# 1_P1_schdoc.net
KiCad netlist of a schematic drawn in Altium Designer
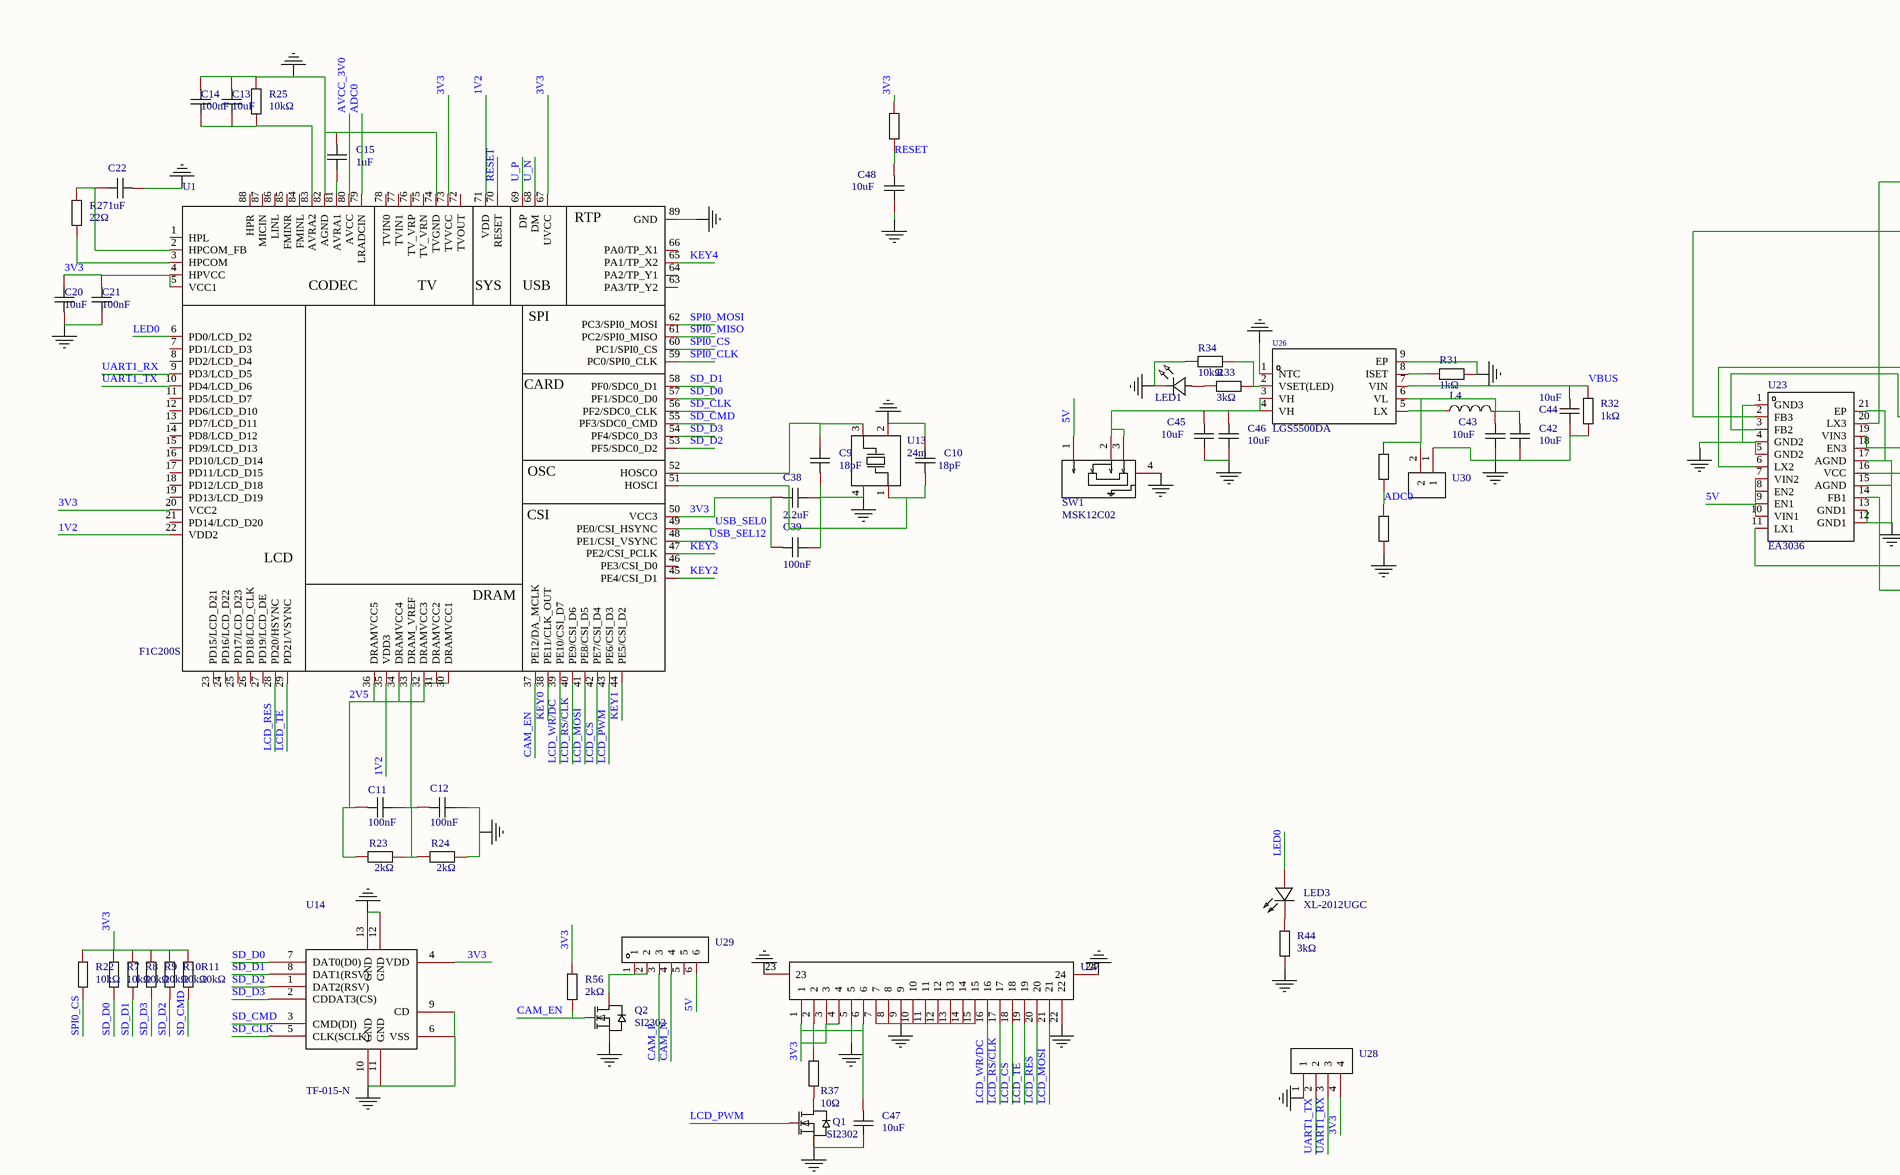
[diagram p0: 1_P1.schdoc.schdoc, top left]
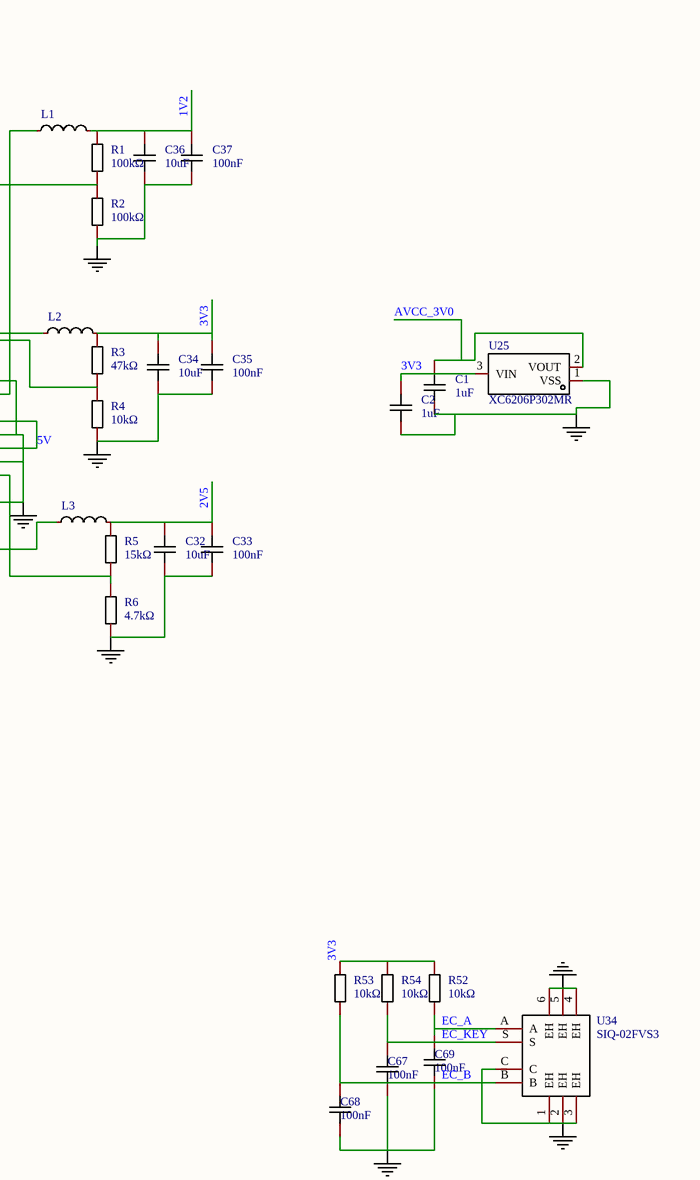
[diagram p1: 1_P1.schdoc.schdoc, top right]
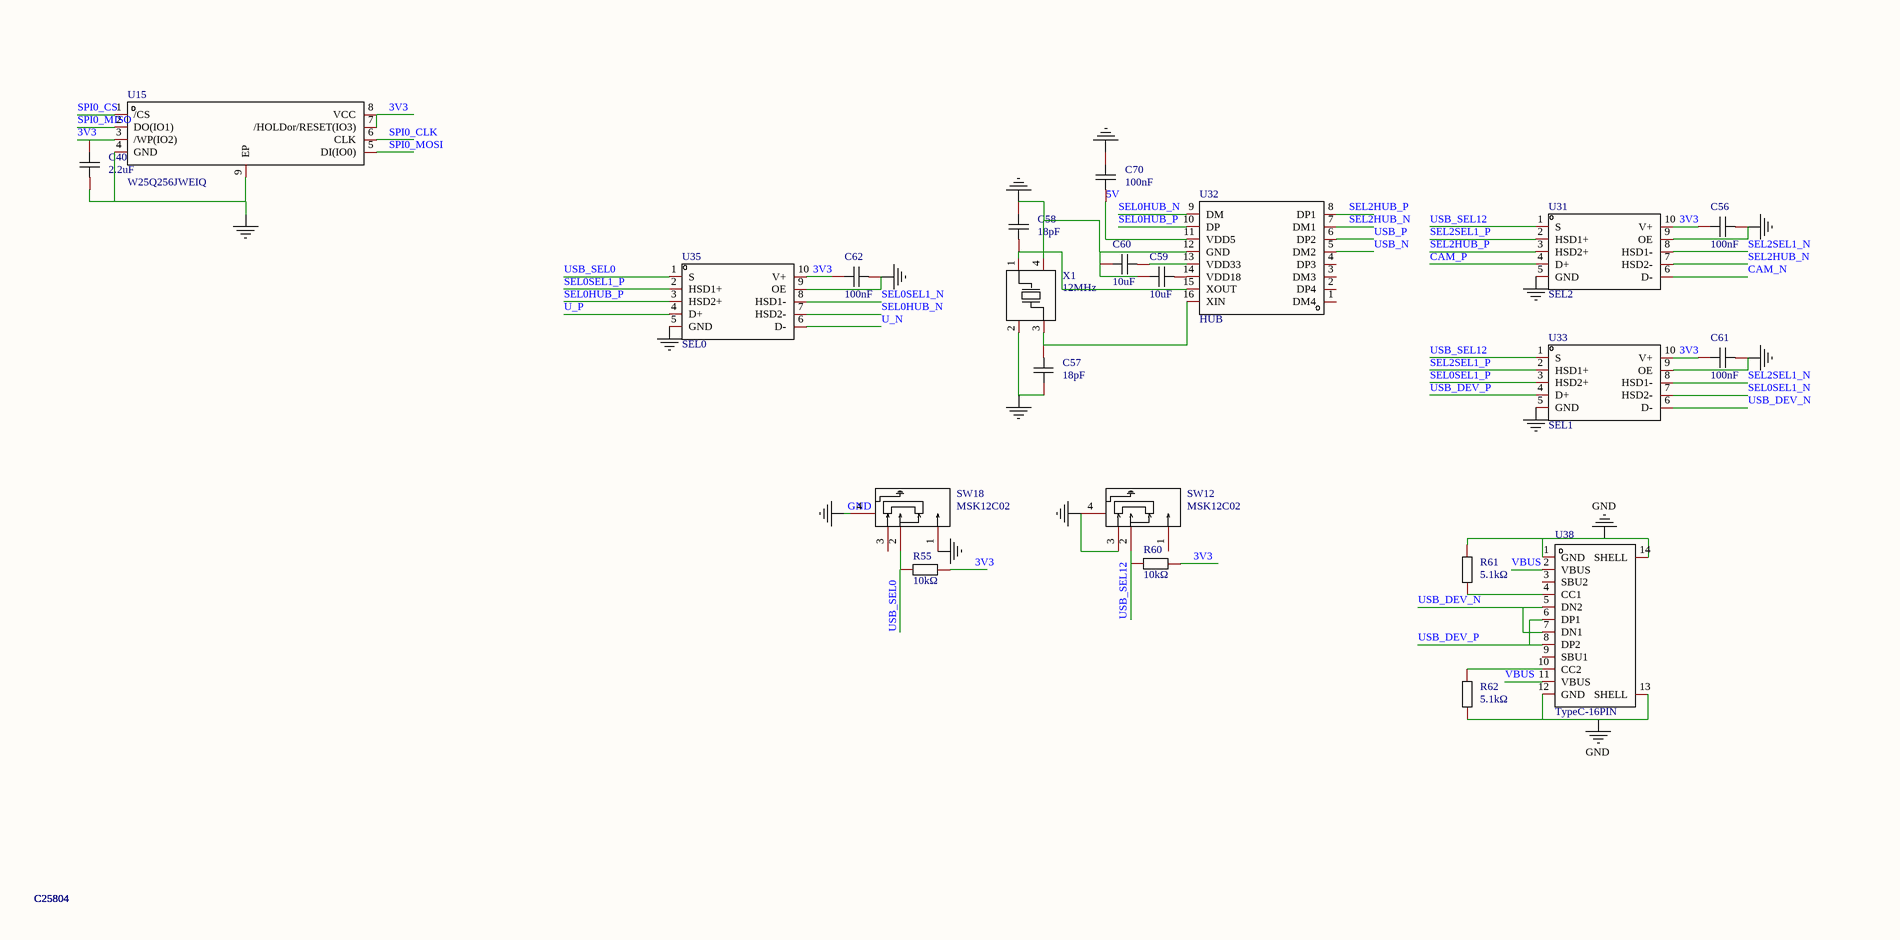
[diagram p2: 1_P1.schdoc.schdoc, bottom left]
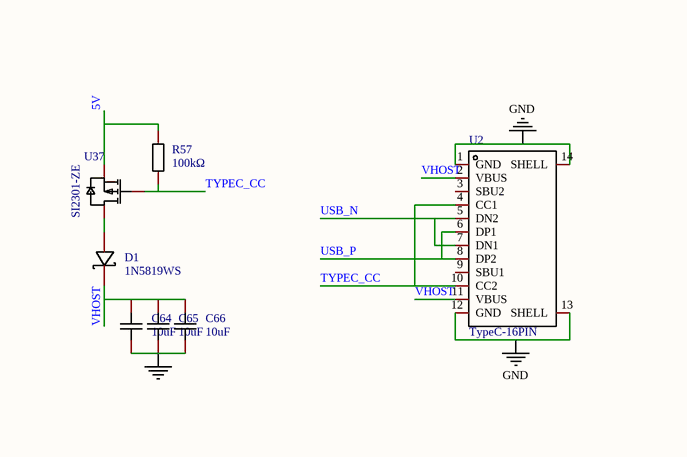
[diagram p3: 1_P1.schdoc.schdoc, bottom right]

(export (version "E")
  (design (tool "Eeschema 10.0.6"))
  (components
    (comp (ref "C1")
      (value "1uF")
      (fields
        (field (name "NAME") "1uF")
        (field (name "MANUFACTURER") "SAMSUNG(三星)")
        (field (name "MANUFACTURER PART") "CL10A105KB8NNNC")
        (field (name "TOLERANCE") "±10%")
      )
      (libsource (lib "altium-import") (part "root_1_CL10A105KB8NNNC_"))
    )
    (comp (ref "C2")
      (value "1uF")
      (fields
        (field (name "NAME") "1uF")
        (field (name "MANUFACTURER") "SAMSUNG(三星)")
        (field (name "MANUFACTURER PART") "CL10A105KB8NNNC")
        (field (name "TOLERANCE") "±10%")
      )
      (libsource (lib "altium-import") (part "root_1_CL10A105KB8NNNC_"))
    )
    (comp (ref "C9")
      (value "18pF")
      (fields
        (field (name "NAME") "18pF")
        (field (name "MANUFACTURER") "FH(风华)")
        (field (name "MANUFACTURER PART") "0402CG180J500NT")
        (field (name "TOLERANCE") "±5%")
      )
      (libsource (lib "altium-import") (part "root_3_0402CG180J500NT_"))
    )
    (comp (ref "C10")
      (value "18pF")
      (fields
        (field (name "NAME") "18pF")
        (field (name "MANUFACTURER") "FH(风华)")
        (field (name "MANUFACTURER PART") "0402CG180J500NT")
        (field (name "TOLERANCE") "±5%")
      )
      (libsource (lib "altium-import") (part "root_3_0402CG180J500NT_"))
    )
    (comp (ref "C11")
      (value "100nF")
      (fields
        (field (name "NAME") "100nF")
        (field (name "MANUFACTURER") "FH(风华)")
        (field (name "MANUFACTURER PART") "0603B104K500NT")
        (field (name "TOLERANCE") "±10%")
      )
      (libsource (lib "altium-import") (part "root_2_0603B104K500NT_"))
    )
    (comp (ref "C12")
      (value "100nF")
      (fields
        (field (name "NAME") "100nF")
        (field (name "MANUFACTURER") "FH(风华)")
        (field (name "MANUFACTURER PART") "0603B104K500NT")
        (field (name "TOLERANCE") "±10%")
      )
      (libsource (lib "altium-import") (part "root_2_0603B104K500NT_"))
    )
    (comp (ref "C13")
      (value "10uF")
      (fields
        (field (name "NAME") "10uF")
        (field (name "MANUFACTURER") "SAMSUNG(三星)")
        (field (name "MANUFACTURER PART") "CL10A106MA8NRNC")
        (field (name "TOLERANCE") "±20%")
      )
      (libsource (lib "altium-import") (part "root_1_CL10A106MA8NRNC_"))
    )
    (comp (ref "C14")
      (value "100nF")
      (fields
        (field (name "NAME") "100nF")
        (field (name "MANUFACTURER") "FH(风华)")
        (field (name "MANUFACTURER PART") "0603B104K500NT")
        (field (name "TOLERANCE") "±10%")
      )
      (libsource (lib "altium-import") (part "root_1_0603B104K500NT_"))
    )
    (comp (ref "C15")
      (value "1uF")
      (fields
        (field (name "NAME") "1uF")
        (field (name "MANUFACTURER") "SAMSUNG(三星)")
        (field (name "MANUFACTURER PART") "CL10A105KB8NNNC")
        (field (name "TOLERANCE") "±10%")
      )
      (libsource (lib "altium-import") (part "root_1_CL10A105KB8NNNC_"))
    )
    (comp (ref "C20")
      (value "10uF")
      (fields
        (field (name "NAME") "10uF")
        (field (name "MANUFACTURER") "SAMSUNG(三星)")
        (field (name "MANUFACTURER PART") "CL10A106MA8NRNC")
        (field (name "TOLERANCE") "±20%")
      )
      (libsource (lib "altium-import") (part "root_3_CL10A106MA8NRNC_"))
    )
    (comp (ref "C21")
      (value "100nF")
      (fields
        (field (name "NAME") "100nF")
        (field (name "MANUFACTURER") "FH(风华)")
        (field (name "MANUFACTURER PART") "0603B104K500NT")
        (field (name "TOLERANCE") "±10%")
      )
      (libsource (lib "altium-import") (part "root_1_0603B104K500NT_"))
    )
    (comp (ref "C22")
      (value "1uF")
      (fields
        (field (name "NAME") "1uF")
        (field (name "MANUFACTURER") "SAMSUNG(三星)")
        (field (name "MANUFACTURER PART") "CL10A105KB8NNNC")
        (field (name "TOLERANCE") "±10%")
      )
      (libsource (lib "altium-import") (part "root_0_CL10A105KB8NNNC_"))
    )
    (comp (ref "C32")
      (value "10uF")
      (fields
        (field (name "NAME") "10uF")
        (field (name "MANUFACTURER") "SAMSUNG(三星)")
        (field (name "MANUFACTURER PART") "CL10A106MA8NRNC")
        (field (name "TOLERANCE") "±20%")
      )
      (libsource (lib "altium-import") (part "root_3_CL10A106MA8NRNC_"))
    )
    (comp (ref "C33")
      (value "100nF")
      (fields
        (field (name "NAME") "100nF")
        (field (name "MANUFACTURER") "FH(风华)")
        (field (name "MANUFACTURER PART") "0603B104K500NT")
        (field (name "TOLERANCE") "±10%")
      )
      (libsource (lib "altium-import") (part "root_3_0603B104K500NT_"))
    )
    (comp (ref "C34")
      (value "10uF")
      (fields
        (field (name "NAME") "10uF")
        (field (name "MANUFACTURER") "SAMSUNG(三星)")
        (field (name "MANUFACTURER PART") "CL10A106MA8NRNC")
        (field (name "TOLERANCE") "±20%")
      )
      (libsource (lib "altium-import") (part "root_3_CL10A106MA8NRNC_"))
    )
    (comp (ref "C35")
      (value "100nF")
      (fields
        (field (name "NAME") "100nF")
        (field (name "MANUFACTURER") "FH(风华)")
        (field (name "MANUFACTURER PART") "0603B104K500NT")
        (field (name "TOLERANCE") "±10%")
      )
      (libsource (lib "altium-import") (part "root_3_0603B104K500NT_"))
    )
    (comp (ref "C36")
      (value "10uF")
      (fields
        (field (name "NAME") "10uF")
        (field (name "MANUFACTURER") "SAMSUNG(三星)")
        (field (name "MANUFACTURER PART") "CL10A106MA8NRNC")
        (field (name "TOLERANCE") "±20%")
      )
      (libsource (lib "altium-import") (part "root_3_CL10A106MA8NRNC_"))
    )
    (comp (ref "C37")
      (value "100nF")
      (fields
        (field (name "NAME") "100nF")
        (field (name "MANUFACTURER") "FH(风华)")
        (field (name "MANUFACTURER PART") "0603B104K500NT")
        (field (name "TOLERANCE") "±10%")
      )
      (libsource (lib "altium-import") (part "root_3_0603B104K500NT_"))
    )
    (comp (ref "C38")
      (value "2.2uF")
      (fields
        (field (name "NAME") "2.2uF")
        (field (name "MANUFACTURER") "SAMSUNG(三星)")
        (field (name "MANUFACTURER PART") "CL10A225KO8NNNC")
        (field (name "TOLERANCE") "±10%")
      )
      (libsource (lib "altium-import") (part "root_2_CL10A225KO8NNNC_"))
    )
    (comp (ref "C39")
      (value "100nF")
      (fields
        (field (name "NAME") "100nF")
        (field (name "MANUFACTURER") "FH(风华)")
        (field (name "MANUFACTURER PART") "0603B104K500NT")
        (field (name "TOLERANCE") "±10%")
      )
      (libsource (lib "altium-import") (part "root_2_0603B104K500NT_"))
    )
    (comp (ref "C40")
      (value "2.2uF")
      (fields
        (field (name "NAME") "2.2uF")
        (field (name "MANUFACTURER") "SAMSUNG(三星)")
        (field (name "MANUFACTURER PART") "CL10A225KO8NNNC")
        (field (name "TOLERANCE") "±10%")
      )
      (libsource (lib "altium-import") (part "root_3_CL10A225KO8NNNC_"))
    )
    (comp (ref "C42")
      (value "10uF")
      (fields
        (field (name "NAME") "10uF")
        (field (name "MANUFACTURER") "SAMSUNG(三星)")
        (field (name "MANUFACTURER PART") "CL10A106MA8NRNC")
        (field (name "TOLERANCE") "±20%")
      )
      (libsource (lib "altium-import") (part "root_1_CL10A106MA8NRNC_"))
    )
    (comp (ref "C43")
      (value "10uF")
      (fields
        (field (name "NAME") "10uF")
        (field (name "MANUFACTURER") "SAMSUNG(三星)")
        (field (name "MANUFACTURER PART") "CL10A106MA8NRNC")
        (field (name "TOLERANCE") "±20%")
      )
      (libsource (lib "altium-import") (part "root_1_CL10A106MA8NRNC_"))
    )
    (comp (ref "C44")
      (value "10uF")
      (fields
        (field (name "NAME") "10uF")
        (field (name "MANUFACTURER") "SAMSUNG(三星)")
        (field (name "MANUFACTURER PART") "CL10A106MA8NRNC")
        (field (name "TOLERANCE") "±20%")
      )
      (libsource (lib "altium-import") (part "root_1_CL10A106MA8NRNC_"))
    )
    (comp (ref "C45")
      (value "10uF")
      (fields
        (field (name "NAME") "10uF")
        (field (name "MANUFACTURER") "SAMSUNG(三星)")
        (field (name "MANUFACTURER PART") "CL10A106MA8NRNC")
        (field (name "TOLERANCE") "±20%")
      )
      (libsource (lib "altium-import") (part "root_1_CL10A106MA8NRNC_"))
    )
    (comp (ref "C46")
      (value "10uF")
      (fields
        (field (name "NAME") "10uF")
        (field (name "MANUFACTURER") "SAMSUNG(三星)")
        (field (name "MANUFACTURER PART") "CL10A106MA8NRNC")
        (field (name "TOLERANCE") "±20%")
      )
      (libsource (lib "altium-import") (part "root_1_CL10A106MA8NRNC_"))
    )
    (comp (ref "C47")
      (value "10uF")
      (fields
        (field (name "NAME") "10uF")
        (field (name "MANUFACTURER") "SAMSUNG(三星)")
        (field (name "MANUFACTURER PART") "CL10A106MA8NRNC")
        (field (name "TOLERANCE") "±20%")
      )
      (libsource (lib "altium-import") (part "root_1_CL10A106MA8NRNC_"))
    )
    (comp (ref "C48")
      (value "10uF")
      (fields
        (field (name "NAME") "10uF")
        (field (name "MANUFACTURER") "SAMSUNG(三星)")
        (field (name "MANUFACTURER PART") "CL10A106MA8NRNC")
        (field (name "TOLERANCE") "±20%")
      )
      (libsource (lib "altium-import") (part "root_1_CL10A106MA8NRNC_"))
    )
    (comp (ref "C56")
      (value "100nF")
      (fields
        (field (name "NAME") "100nF")
        (field (name "MANUFACTURER") "FH(风华)")
        (field (name "MANUFACTURER PART") "0603B104K500NT")
        (field (name "TOLERANCE") "±10%")
      )
      (libsource (lib "altium-import") (part "root_0_0603B104K500NT_"))
    )
    (comp (ref "C57")
      (value "18pF")
      (fields
        (field (name "NAME") "18pF")
        (field (name "MANUFACTURER") "FH(风华)")
        (field (name "MANUFACTURER PART") "0402CG180J500NT")
        (field (name "TOLERANCE") "±5%")
      )
      (libsource (lib "altium-import") (part "root_1_0402CG180J500NT_"))
    )
    (comp (ref "C58")
      (value "18pF")
      (fields
        (field (name "NAME") "18pF")
        (field (name "MANUFACTURER") "FH(风华)")
        (field (name "MANUFACTURER PART") "0402CG180J500NT")
        (field (name "TOLERANCE") "±5%")
      )
      (libsource (lib "altium-import") (part "root_3_0402CG180J500NT_"))
    )
    (comp (ref "C59")
      (value "10uF")
      (fields
        (field (name "NAME") "10uF")
        (field (name "MANUFACTURER") "SAMSUNG(三星)")
        (field (name "MANUFACTURER PART") "CL10A106MA8NRNC")
        (field (name "TOLERANCE") "±20%")
      )
      (libsource (lib "altium-import") (part "root_0_CL10A106MA8NRNC_"))
    )
    (comp (ref "C60")
      (value "10uF")
      (fields
        (field (name "NAME") "10uF")
        (field (name "MANUFACTURER") "SAMSUNG(三星)")
        (field (name "MANUFACTURER PART") "CL10A106MA8NRNC")
        (field (name "TOLERANCE") "±20%")
      )
      (libsource (lib "altium-import") (part "root_0_CL10A106MA8NRNC_"))
    )
    (comp (ref "C61")
      (value "100nF")
      (fields
        (field (name "NAME") "100nF")
        (field (name "MANUFACTURER") "FH(风华)")
        (field (name "MANUFACTURER PART") "0603B104K500NT")
        (field (name "TOLERANCE") "±10%")
      )
      (libsource (lib "altium-import") (part "root_0_0603B104K500NT_"))
    )
    (comp (ref "C62")
      (value "100nF")
      (fields
        (field (name "NAME") "100nF")
        (field (name "MANUFACTURER") "FH(风华)")
        (field (name "MANUFACTURER PART") "0603B104K500NT")
        (field (name "TOLERANCE") "±10%")
      )
      (libsource (lib "altium-import") (part "root_0_0603B104K500NT_"))
    )
    (comp (ref "C64")
      (value "10uF")
      (fields
        (field (name "NAME") "10uF")
        (field (name "MANUFACTURER") "SAMSUNG(三星)")
        (field (name "MANUFACTURER PART") "CL10A106MA8NRNC")
        (field (name "TOLERANCE") "±20%")
      )
      (libsource (lib "altium-import") (part "root_3_CL10A106MA8NRNC_"))
    )
    (comp (ref "C65")
      (value "10uF")
      (fields
        (field (name "NAME") "10uF")
        (field (name "MANUFACTURER") "SAMSUNG(三星)")
        (field (name "MANUFACTURER PART") "CL10A106MA8NRNC")
        (field (name "TOLERANCE") "±20%")
      )
      (libsource (lib "altium-import") (part "root_3_CL10A106MA8NRNC_"))
    )
    (comp (ref "C66")
      (value "10uF")
      (fields
        (field (name "NAME") "10uF")
        (field (name "MANUFACTURER") "SAMSUNG(三星)")
        (field (name "MANUFACTURER PART") "CL10A106MA8NRNC")
        (field (name "TOLERANCE") "±20%")
      )
      (libsource (lib "altium-import") (part "root_3_CL10A106MA8NRNC_"))
    )
    (comp (ref "C67")
      (value "100nF")
      (fields
        (field (name "NAME") "100nF")
        (field (name "MANUFACTURER") "FH(风华)")
        (field (name "MANUFACTURER PART") "0603B104K500NT")
        (field (name "TOLERANCE") "±10%")
      )
      (libsource (lib "altium-import") (part "root_1_0603B104K500NT_"))
    )
    (comp (ref "C68")
      (value "100nF")
      (fields
        (field (name "NAME") "100nF")
        (field (name "MANUFACTURER") "FH(风华)")
        (field (name "MANUFACTURER PART") "0603B104K500NT")
        (field (name "TOLERANCE") "±10%")
      )
      (libsource (lib "altium-import") (part "root_1_0603B104K500NT_"))
    )
    (comp (ref "C69")
      (value "100nF")
      (fields
        (field (name "NAME") "100nF")
        (field (name "MANUFACTURER") "FH(风华)")
        (field (name "MANUFACTURER PART") "0603B104K500NT")
        (field (name "TOLERANCE") "±10%")
      )
      (libsource (lib "altium-import") (part "root_1_0603B104K500NT_"))
    )
    (comp (ref "C70")
      (value "100nF")
      (fields
        (field (name "NAME") "100nF")
        (field (name "MANUFACTURER") "FH(风华)")
        (field (name "MANUFACTURER PART") "0603B104K500NT")
        (field (name "TOLERANCE") "±10%")
      )
      (libsource (lib "altium-import") (part "root_3_0603B104K500NT_"))
    )
    (comp (ref "D1")
      (value "1N5819WS")
      (description "正向压降(Vf):600mV@1A;直流反向耐压(Vr):40V;平均整流电流(Io):1A;")
      (fields (field (name "NAME") "1N5819WS") (field (name "MANUFACTURER") "Hottech(合科泰)"))
      (libsource (lib "altium-import") (part "root_1_1N5819WS_C191023_"))
    )
    (comp (ref "L1")
      (value "2.2uH")
      (fields
        (field (name "MANUFACTURER") "Cybermax(思博科技)")
        (field (name "MANUFACTURER PART") "CMLW252012S2R2MST")
        (field (name "TOLERANCE") "±20%")
      )
      (libsource (lib "altium-import") (part "root_0_CMLW252012S2R2MST_"))
    )
    (comp (ref "L2")
      (value "2.2uH")
      (fields
        (field (name "MANUFACTURER") "Cybermax(思博科技)")
        (field (name "MANUFACTURER PART") "CMLW252012S2R2MST")
        (field (name "TOLERANCE") "±20%")
      )
      (libsource (lib "altium-import") (part "root_0_CMLW252012S2R2MST_"))
    )
    (comp (ref "L3")
      (value "2.2uH")
      (fields
        (field (name "MANUFACTURER") "Cybermax(思博科技)")
        (field (name "MANUFACTURER PART") "CMLW252012S2R2MST")
        (field (name "TOLERANCE") "±20%")
      )
      (libsource (lib "altium-import") (part "root_0_CMLW252012S2R2MST_"))
    )
    (comp (ref "L4")
      (value "2.2uH")
      (fields
        (field (name "MANUFACTURER") "Cybermax(思博科技)")
        (field (name "MANUFACTURER PART") "CMLW252012S2R2MST")
        (field (name "TOLERANCE") "±20%")
      )
      (libsource (lib "altium-import") (part "root_0_CMLW252012S2R2MST_"))
    )
    (comp (ref "LED1")
      (value "XL-1608SURC-06")
      (description "发光颜色:红灯;主波长:617nm~621nm;色温:-;功率:55mW;安装方式:正贴;")
      (fields (field (name "MANUFACTURER") "XINGLIGHT(成兴光)"))
      (libsource (lib "altium-import") (part "root_0_XL-1608SURC-06_"))
    )
    (comp (ref "LED3")
      (value "XL-2012UGC")
      (description "发光颜色:翠绿;主波长:516nm~525nm;色温:-;功率:80mW;安装方式:正贴;")
      (fields (field (name "NAME") "XL-2012UGC") (field (name "MANUFACTURER") "XINGLIGHT(成兴光)"))
      (libsource (lib "altium-import") (part "root_1_XL-2012UGC_"))
    )
    (comp (ref "Q1")
      (value "SI2302")
      (fields (field (name "NAME") "SI2302") (field (name "MANUFACTURER") "TECH PUBLIC(台舟)"))
      (libsource (lib "altium-import") (part "root_0_SI2302_"))
    )
    (comp (ref "Q2")
      (value "SI2302")
      (fields (field (name "NAME") "SI2302") (field (name "MANUFACTURER") "TECH PUBLIC(台舟)"))
      (libsource (lib "altium-import") (part "root_0_SI2302_"))
    )
    (comp (ref "R1")
      (value "100kΩ")
      (fields
        (field (name "NAME") "100kΩ")
        (field (name "MANUFACTURER") "YAGEO(国巨)")
        (field (name "MANUFACTURER PART") "RC0603FR-07100KL")
        (field (name "TOLERANCE") "±1%")
      )
      (libsource (lib "altium-import") (part "root_1_RC0603FR-07100KL_"))
    )
    (comp (ref "R2")
      (value "100kΩ")
      (fields
        (field (name "NAME") "100kΩ")
        (field (name "MANUFACTURER") "YAGEO(国巨)")
        (field (name "MANUFACTURER PART") "RC0603FR-07100KL")
        (field (name "TOLERANCE") "±1%")
      )
      (libsource (lib "altium-import") (part "root_1_RC0603FR-07100KL_"))
    )
    (comp (ref "R3")
      (value "47kΩ")
      (fields
        (field (name "NAME") "47kΩ")
        (field (name "MANUFACTURER") "UNI-ROYAL(厚声)")
        (field (name "MANUFACTURER PART") "0603WAF4702T5E")
        (field (name "TOLERANCE") "±1%")
      )
      (libsource (lib "altium-import") (part "root_1_0603WAF4702T5E_"))
    )
    (comp (ref "R4")
      (value "10kΩ")
      (description "阻值:10kΩ;精度:±1%;功率:100mW;温度系数:±100ppm/℃;电阻类型:厚膜电阻;")
      (fields
        (field (name "NAME") "10kΩ")
        (field (name "MANUFACTURER") "UNI-ROYAL(厚声)")
        (field (name "MANUFACTURER PART") "0603WAF1002T5E")
      )
      (libsource (lib "altium-import") (part "root_1_0603WAF1002T5E_"))
    )
    (comp (ref "R5")
      (value "15kΩ")
      (fields
        (field (name "NAME") "15kΩ")
        (field (name "MANUFACTURER") "UNI-ROYAL(厚声)")
        (field (name "MANUFACTURER PART") "0603WAF1502T5E")
        (field (name "TOLERANCE") "±1%")
      )
      (libsource (lib "altium-import") (part "root_1_0603WAF1502T5E_"))
    )
    (comp (ref "R6")
      (value "4.7kΩ")
      (fields
        (field (name "NAME") "4.7kΩ")
        (field (name "MANUFACTURER") "UNI-ROYAL(厚声)")
        (field (name "MANUFACTURER PART") "0603WAF4701T5E")
        (field (name "TOLERANCE") "±1%")
      )
      (libsource (lib "altium-import") (part "root_1_0603WAF4701T5E_"))
    )
    (comp (ref "R7")
      (value "10kΩ")
      (description "阻值:10kΩ;精度:±1%;功率:100mW;温度系数:±100ppm/℃;电阻类型:厚膜电阻;")
      (fields
        (field (name "NAME") "10kΩ")
        (field (name "SUPPLIER PART") "C25804")
        (field (name "MANUFACTURER") "UNI-ROYAL(厚声)")
        (field (name "MANUFACTURER PART") "0603WAF1002T5E")
      )
      (libsource (lib "altium-import") (part "root_1_0603WAF1002T5E_"))
    )
    (comp (ref "R8")
      (value "10kΩ")
      (description "阻值:10kΩ;精度:±1%;功率:100mW;温度系数:±100ppm/℃;电阻类型:厚膜电阻;")
      (fields
        (field (name "NAME") "10kΩ")
        (field (name "SUPPLIER PART") "C25804")
        (field (name "MANUFACTURER") "UNI-ROYAL(厚声)")
        (field (name "MANUFACTURER PART") "0603WAF1002T5E")
      )
      (libsource (lib "altium-import") (part "root_1_0603WAF1002T5E_"))
    )
    (comp (ref "R9")
      (value "10kΩ")
      (description "阻值:10kΩ;精度:±1%;功率:100mW;温度系数:±100ppm/℃;电阻类型:厚膜电阻;")
      (fields
        (field (name "NAME") "10kΩ")
        (field (name "SUPPLIER PART") "C25804")
        (field (name "MANUFACTURER") "UNI-ROYAL(厚声)")
        (field (name "MANUFACTURER PART") "0603WAF1002T5E")
      )
      (libsource (lib "altium-import") (part "root_1_0603WAF1002T5E_"))
    )
    (comp (ref "R10")
      (value "10kΩ")
      (description "阻值:10kΩ;精度:±1%;功率:100mW;温度系数:±100ppm/℃;电阻类型:厚膜电阻;")
      (fields
        (field (name "NAME") "10kΩ")
        (field (name "SUPPLIER PART") "C25804")
        (field (name "MANUFACTURER") "UNI-ROYAL(厚声)")
        (field (name "MANUFACTURER PART") "0603WAF1002T5E")
      )
      (libsource (lib "altium-import") (part "root_1_0603WAF1002T5E_"))
    )
    (comp (ref "R11")
      (value "10kΩ")
      (description "阻值:10kΩ;精度:±1%;功率:100mW;温度系数:±100ppm/℃;电阻类型:厚膜电阻;")
      (fields
        (field (name "NAME") "10kΩ")
        (field (name "SUPPLIER PART") "C25804")
        (field (name "MANUFACTURER") "UNI-ROYAL(厚声)")
        (field (name "MANUFACTURER PART") "0603WAF1002T5E")
      )
      (libsource (lib "altium-import") (part "root_1_0603WAF1002T5E_"))
    )
    (comp (ref "R12")
      (value "10kΩ")
      (description "阻值:10kΩ;精度:±1%;功率:100mW;温度系数:±100ppm/℃;电阻类型:厚膜电阻;")
      (fields
        (field (name "MANUFACTURER") "UNI-ROYAL(厚声)")
        (field (name "MANUFACTURER PART") "0603WAF1002T5E")
      )
      (libsource (lib "altium-import") (part "root_1_0603WAF1002T5E_"))
    )
    (comp (ref "R22")
      (value "10kΩ")
      (description "阻值:10kΩ;精度:±1%;功率:100mW;温度系数:±100ppm/℃;电阻类型:厚膜电阻;")
      (fields
        (field (name "NAME") "10kΩ")
        (field (name "SUPPLIER PART") "C25804")
        (field (name "MANUFACTURER") "UNI-ROYAL(厚声)")
        (field (name "MANUFACTURER PART") "0603WAF1002T5E")
      )
      (libsource (lib "altium-import") (part "root_1_0603WAF1002T5E_"))
    )
    (comp (ref "R23")
      (value "2kΩ")
      (description "阻值:2kΩ;精度:±1%;功率:100mW;温度系数:±100ppm/℃;电阻类型:厚膜电阻;")
      (fields
        (field (name "NAME") "2kΩ")
        (field (name "MANUFACTURER") "UNI-ROYAL(厚声)")
        (field (name "MANUFACTURER PART") "0603WAF2001T5E")
      )
      (libsource (lib "altium-import") (part "root_0_0603WAF2001T5E_"))
    )
    (comp (ref "R24")
      (value "2kΩ")
      (description "阻值:2kΩ;精度:±1%;功率:100mW;温度系数:±100ppm/℃;电阻类型:厚膜电阻;")
      (fields
        (field (name "NAME") "2kΩ")
        (field (name "MANUFACTURER") "UNI-ROYAL(厚声)")
        (field (name "MANUFACTURER PART") "0603WAF2001T5E")
      )
      (libsource (lib "altium-import") (part "root_0_0603WAF2001T5E_"))
    )
    (comp (ref "R25")
      (value "10kΩ")
      (fields
        (field (name "NAME") "10kΩ")
        (field (name "MANUFACTURER") "UNI-ROYAL(厚声)")
        (field (name "MANUFACTURER PART") "0603WAF1002T5E")
        (field (name "TOLERANCE") "±1%")
      )
      (libsource (lib "altium-import") (part "root_3_0603WAF1002T5E_"))
    )
    (comp (ref "R27")
      (value "22Ω")
      (fields
        (field (name "NAME") "22Ω")
        (field (name "MANUFACTURER") "UNI-ROYAL(厚声)")
        (field (name "MANUFACTURER PART") "0603WAF220JT5E")
        (field (name "TOLERANCE") "±1%")
      )
      (libsource (lib "altium-import") (part "root_1_0603WAF220JT5E_"))
    )
    (comp (ref "R31")
      (value "1kΩ")
      (fields
        (field (name "NAME") "1kΩ")
        (field (name "MANUFACTURER") "UNI-ROYAL(厚声)")
        (field (name "MANUFACTURER PART") "0603WAF1001T5E")
        (field (name "TOLERANCE") "±1%")
      )
      (libsource (lib "altium-import") (part "root_0_0603WAF1001T5E_"))
    )
    (comp (ref "R32")
      (value "1kΩ")
      (fields
        (field (name "NAME") "1kΩ")
        (field (name "MANUFACTURER") "UNI-ROYAL(厚声)")
        (field (name "MANUFACTURER PART") "0603WAF1001T5E")
        (field (name "TOLERANCE") "±1%")
      )
      (libsource (lib "altium-import") (part "root_1_0603WAF1001T5E_"))
    )
    (comp (ref "R33")
      (value "3kΩ")
      (fields
        (field (name "NAME") "3kΩ")
        (field (name "MANUFACTURER") "UNI-ROYAL(厚声)")
        (field (name "MANUFACTURER PART") "0603WAF3001T5E")
        (field (name "TOLERANCE") "±1%")
      )
      (libsource (lib "altium-import") (part "root_2_0603WAF3001T5E_"))
    )
    (comp (ref "R34")
      (value "10kΩ")
      (fields
        (field (name "NAME") "10kΩ")
        (field (name "MANUFACTURER") "UNI-ROYAL(厚声)")
        (field (name "MANUFACTURER PART") "0603WAF1002T5E")
        (field (name "TOLERANCE") "±1%")
      )
      (libsource (lib "altium-import") (part "root_0_0603WAF1002T5E_"))
    )
    (comp (ref "R37")
      (value "10Ω")
      (fields
        (field (name "NAME") "10Ω")
        (field (name "MANUFACTURER") "UNI-ROYAL(厚声)")
        (field (name "MANUFACTURER PART") "0603WAF100JT5E")
        (field (name "TOLERANCE") "±1%")
      )
      (libsource (lib "altium-import") (part "root_1_0603WAF100JT5E_"))
    )
    (comp (ref "R44")
      (value "3kΩ")
      (fields
        (field (name "NAME") "3kΩ")
        (field (name "MANUFACTURER") "UNI-ROYAL(厚声)")
        (field (name "MANUFACTURER PART") "0603WAF3001T5E")
        (field (name "TOLERANCE") "±1%")
      )
      (libsource (lib "altium-import") (part "root_3_0603WAF3001T5E_"))
    )
    (comp (ref "R50")
      (value "10kΩ")
      (description "阻值:10kΩ;精度:±1%;功率:100mW;温度系数:±100ppm/℃;电阻类型:厚膜电阻;")
      (fields
        (field (name "MANUFACTURER") "UNI-ROYAL(厚声)")
        (field (name "MANUFACTURER PART") "0603WAF1002T5E")
      )
      (libsource (lib "altium-import") (part "root_1_0603WAF1002T5E_"))
    )
    (comp (ref "R51")
      (value "10kΩ")
      (description "阻值:10kΩ;精度:±1%;功率:100mW;温度系数:±100ppm/℃;电阻类型:厚膜电阻;")
      (fields
        (field (name "MANUFACTURER") "UNI-ROYAL(厚声)")
        (field (name "MANUFACTURER PART") "0603WAF1002T5E")
      )
      (libsource (lib "altium-import") (part "root_1_0603WAF1002T5E_"))
    )
    (comp (ref "R52")
      (value "10kΩ")
      (fields
        (field (name "NAME") "10kΩ")
        (field (name "MANUFACTURER") "UNI-ROYAL(厚声)")
        (field (name "MANUFACTURER PART") "0603WAF1002T5E")
        (field (name "TOLERANCE") "±1%")
      )
      (libsource (lib "altium-import") (part "root_1_0603WAF1002T5E_"))
    )
    (comp (ref "R53")
      (value "10kΩ")
      (fields
        (field (name "NAME") "10kΩ")
        (field (name "MANUFACTURER") "UNI-ROYAL(厚声)")
        (field (name "MANUFACTURER PART") "0603WAF1002T5E")
        (field (name "TOLERANCE") "±1%")
      )
      (libsource (lib "altium-import") (part "root_1_0603WAF1002T5E_"))
    )
    (comp (ref "R54")
      (value "10kΩ")
      (fields
        (field (name "NAME") "10kΩ")
        (field (name "MANUFACTURER") "UNI-ROYAL(厚声)")
        (field (name "MANUFACTURER PART") "0603WAF1002T5E")
        (field (name "TOLERANCE") "±1%")
      )
      (libsource (lib "altium-import") (part "root_1_0603WAF1002T5E_"))
    )
    (comp (ref "R55")
      (value "10kΩ")
      (description "阻值:10kΩ;精度:±1%;功率:100mW;温度系数:±100ppm/℃;电阻类型:厚膜电阻;")
      (fields
        (field (name "NAME") "10kΩ")
        (field (name "MANUFACTURER") "UNI-ROYAL(厚声)")
        (field (name "MANUFACTURER PART") "0603WAF1002T5E")
      )
      (libsource (lib "altium-import") (part "root_2_0603WAF1002T5E_"))
    )
    (comp (ref "R56")
      (value "2kΩ")
      (description "阻值:2kΩ;精度:±1%;功率:100mW;温度系数:±100ppm/℃;电阻类型:厚膜电阻;")
      (fields
        (field (name "NAME") "2kΩ")
        (field (name "MANUFACTURER") "UNI-ROYAL(厚声)")
        (field (name "MANUFACTURER PART") "0603WAF2001T5E")
      )
      (libsource (lib "altium-import") (part "root_1_0603WAF2001T5E_"))
    )
    (comp (ref "R57")
      (value "100kΩ")
      (fields
        (field (name "NAME") "100kΩ")
        (field (name "MANUFACTURER") "UNI-ROYAL(厚声)")
        (field (name "MANUFACTURER PART") "0603WAF1002T5E")
        (field (name "TOLERANCE") "±1%")
      )
      (libsource (lib "altium-import") (part "root_3_0603WAF1002T5E_"))
    )
    (comp (ref "R60")
      (value "10kΩ")
      (description "阻值:10kΩ;精度:±1%;功率:100mW;温度系数:±100ppm/℃;电阻类型:厚膜电阻;")
      (fields
        (field (name "NAME") "10kΩ")
        (field (name "MANUFACTURER") "UNI-ROYAL(厚声)")
        (field (name "MANUFACTURER PART") "0603WAF1002T5E")
      )
      (libsource (lib "altium-import") (part "root_2_0603WAF1002T5E_"))
    )
    (comp (ref "R61")
      (value "5.1kΩ")
      (fields
        (field (name "NAME") "5.1kΩ")
        (field (name "MANUFACTURER PART") "0603WAF5101T5E")
        (field (name "MANUFACTURER") "UNI-ROYAL(厚声)")
        (field (name "TOLERANCE") "±1%")
      )
      (libsource (lib "altium-import") (part "root_3_0603WAF5101T5E_"))
    )
    (comp (ref "R62")
      (value "5.1kΩ")
      (fields
        (field (name "NAME") "5.1kΩ")
        (field (name "MANUFACTURER PART") "0603WAF5101T5E")
        (field (name "MANUFACTURER") "UNI-ROYAL(厚声)")
        (field (name "TOLERANCE") "±1%")
      )
      (libsource (lib "altium-import") (part "root_1_0603WAF5101T5E_"))
    )
    (comp (ref "SW1")
      (value "MSK12C02")
      (description "电路结构:单刀双掷;安装方式:卧贴;开关颜色:-;额定电流(DC):50mA;额定电压(DC):12V;额定电流(AC):-;额定电压(AC):-;机械寿命:1万次;")
      (fields (field (name "NAME") "MSK12C02") (field (name "MANUFACTURER") "SHOU HAN(首韩)"))
      (libsource (lib "altium-import") (part "root_0_MSK12C02_"))
    )
    (comp (ref "SW12")
      (value "MSK12C02")
      (description "电路结构:单刀双掷;安装方式:卧贴;开关颜色:-;额定电流(DC):50mA;额定电压(DC):12V;额定电流(AC):-;额定电压(AC):-;机械寿命:1万次;")
      (fields (field (name "NAME") "MSK12C02") (field (name "MANUFACTURER") "SHOU HAN(首韩)"))
      (libsource (lib "altium-import") (part "root_2_MSK12C02_"))
    )
    (comp (ref "SW18")
      (value "MSK12C02")
      (description "电路结构:单刀双掷;安装方式:卧贴;开关颜色:-;额定电流(DC):50mA;额定电压(DC):12V;额定电流(AC):-;额定电压(AC):-;机械寿命:1万次;")
      (fields (field (name "NAME") "MSK12C02") (field (name "MANUFACTURER") "SHOU HAN(首韩)"))
      (libsource (lib "altium-import") (part "root_2_MSK12C02_"))
    )
    (comp (ref "U1")
      (value "F1C200S")
      (description "CPU内核:-;CPU最大主频:-;程序存储容量:-;程序存储器类型:-;RAM总容量:-;GPIO端口数量:-;ADC(位数):-;工作温度范围:-;")
      (fields (field (name "NAME") "F1C200S") (field (name "MANUFACTURER") "Allwinner(全志)"))
      (libsource (lib "altium-import") (part "root_0_F1C200S_"))
    )
    (comp (ref "U2")
      (value "TypeC-16PIN")
      (fields (field (name "NAME") "TypeC-16PIN"))
      (libsource (lib "altium-import") (part "root_0_TypeC-16PIN_"))
    )
    (comp (ref "U13")
      (value "24m")
      (fields (field (name "NAME") "24m"))
      (libsource (lib "altium-import") (part "root_1_24m_"))
    )
    (comp (ref "U14")
      (value "TF-015-N")
      (description "连接器类型:卡座;")
      (fields (field (name "NAME") "TF-015-N") (field (name "MANUFACTURER") "HanElectricity(瀚源)"))
      (libsource (lib "altium-import") (part "root_0_TF-015-N_"))
    )
    (comp (ref "U15")
      (value "W25Q256JWEIQ")
      (fields (field (name "NAME") "W25Q256JWEIQ") (field (name "MANUFACTURER") "WINBOND(华邦)"))
      (libsource (lib "altium-import") (part "root_0_W25Q256JWEIQ_C2940048_"))
    )
    (comp (ref "U23")
      (value "EA3036")
      (fields (field (name "NAME") "EA3036"))
      (libsource (lib "altium-import") (part "root_0_EA3036_"))
    )
    (comp (ref "U25")
      (value "XC6206P302MR")
      (description "输出类型:固定;输出极性:正;最大输入电压:8V;输出电压:3V;输出电流:250mA;电源纹波抑制比(PSRR):40dB@(1kHz);")
      (fields (field (name "NAME") "XC6206P302MR") (field (name "MANUFACTURER") "UMW(友台半导体)"))
      (libsource (lib "altium-import") (part "root_2_XC6206P302MR_C347375_"))
    )
    (comp (ref "U26")
      (value "LGS5500DA")
      (description "电池类型:锂离子/聚合物;电池节数:1;最大充电电流:1A;电源电压:4.5V~5.5V;")
      (fields (field (name "NAME") "LGS5500DA") (field (name "MANUFACTURER") "Legend-Si(棱晶半导体)"))
      (libsource (lib "altium-import") (part "root_0_LGS5500DA_"))
    )
    (comp (ref "U27") (value "2.0寸ips") (libsource (lib "altium-import") (part "root_0_2.0寸ips_")))
    (comp (ref "U28") (value "UART2.54") (libsource (lib "altium-import") (part "root_0_UART2.54_")))
    (comp (ref "U29") (value "ir") (libsource (lib "altium-import") (part "root_0_ir_")))
    (comp (ref "U30") (value "bat") (libsource (lib "altium-import") (part "root_2_bat_")))
    (comp (ref "U31")
      (value "SEL2")
      (description "开关电路:-;多路复用器/解复用器电路:-;导通电阻（最大值）:-;开关电压（最大值）:-;")
      (fields (field (name "NAME") "SEL2") (field (name "MANUFACTURER") "杭州瑞盟"))
      (libsource (lib "altium-import") (part "root_0_MSUSB30_"))
    )
    (comp (ref "U32")
      (value "HUB")
      (description "应用功能:集线器;接口协议:-;")
      (fields (field (name "NAME") "HUB") (field (name "MANUFACTURER") "CoreChips(和芯润德)"))
      (libsource (lib "altium-import") (part "root_2_SL2.1A_"))
    )
    (comp (ref "U33")
      (value "SEL1")
      (description "开关电路:-;多路复用器/解复用器电路:-;导通电阻（最大值）:-;开关电压（最大值）:-;")
      (fields (field (name "NAME") "SEL1") (field (name "MANUFACTURER") "杭州瑞盟"))
      (libsource (lib "altium-import") (part "root_0_MSUSB30_"))
    )
    (comp (ref "U34")
      (value "SIQ-02FVS3")
      (fields (field (name "NAME") "SIQ-02FVS3") (field (name "MANUFACTURER") "MITSUMI(美上美)"))
      (libsource (lib "altium-import") (part "root_3_SIQ-02FVS3_"))
    )
    (comp (ref "U35")
      (value "SEL0")
      (description "开关电路:-;多路复用器/解复用器电路:-;导通电阻（最大值）:-;开关电压（最大值）:-;")
      (fields (field (name "NAME") "SEL0") (field (name "MANUFACTURER") "杭州瑞盟"))
      (libsource (lib "altium-import") (part "root_0_MSUSB30_"))
    )
    (comp (ref "U37")
      (value "SI2301-ZE")
      (fields (field (name "NAME") "SI2301-ZE") (field (name "MANUFACTURER") "HXY MOSFET(华轩阳电子)"))
      (libsource (lib "altium-import") (part "root_2_SI2301-ZE_"))
    )
    (comp (ref "U38")
      (value "TypeC-16PIN")
      (fields (field (name "NAME") "TypeC-16PIN"))
      (libsource (lib "altium-import") (part "root_0_TypeC-16PIN_"))
    )
    (comp (ref "X1")
      (value "12MHz")
      (description "晶振类型:贴片晶振;频率:12MHz;常温频差:±10ppm;外接负载电容:20pF;频率稳定度(全温):±20ppm;")
      (fields
        (field (name "NAME") "12MHz")
        (field (name "MANUFACTURER") "YXC(扬兴晶振)")
        (field (name "MANUFACTURER PART") "X322512MSB4SI")
      )
      (libsource (lib "altium-import") (part "root_3_X322512MSB4SI_"))
    )
  )
  (nets
    (net (code "1") (name "/1V2") (class "Default")
      (node (ref "C36") (pin "1") (pinfunction "1_1") (pintype "passive"))
      (node (ref "C37") (pin "1") (pinfunction "1_1") (pintype "passive"))
      (node (ref "L1") (pin "2") (pinfunction "2_2") (pintype "passive"))
      (node (ref "R1") (pin "2") (pinfunction "2_2") (pintype "passive"))
      (node (ref "U1") (pin "22") (pinfunction "VDD2_22") (pintype "passive"))
      (node (ref "U1") (pin "35") (pinfunction "VDD3_35") (pintype "passive"))
      (node (ref "U1") (pin "71") (pinfunction "VDD_71") (pintype "passive"))
    )
    (net (code "2") (name "/2V5") (class "Default")
      (node (ref "C11") (pin "2") (pinfunction "2_2") (pintype "passive"))
      (node (ref "C32") (pin "1") (pinfunction "1_1") (pintype "passive"))
      (node (ref "C33") (pin "1") (pinfunction "1_1") (pintype "passive"))
      (node (ref "L3") (pin "2") (pinfunction "2_2") (pintype "passive"))
      (node (ref "R23") (pin "1") (pinfunction "1_1") (pintype "passive"))
      (node (ref "R5") (pin "2") (pinfunction "2_2") (pintype "passive"))
      (node (ref "U1") (pin "30") (pinfunction "DRAMVCC1_30") (pintype "passive"))
      (node (ref "U1") (pin "31") (pinfunction "DRAMVCC2_31") (pintype "passive"))
      (node (ref "U1") (pin "32") (pinfunction "DRAMVCC3_32") (pintype "passive"))
      (node (ref "U1") (pin "34") (pinfunction "DRAMVCC4_34") (pintype "passive"))
      (node (ref "U1") (pin "36") (pinfunction "DRAMVCC5_36") (pintype "passive"))
    )
    (net (code "3") (name "/3V3") (class "Default")
      (node (ref "C2") (pin "2") (pinfunction "2_2") (pintype "passive"))
      (node (ref "C20") (pin "1") (pinfunction "1_1") (pintype "passive"))
      (node (ref "C21") (pin "2") (pinfunction "2_2") (pintype "passive"))
      (node (ref "C34") (pin "1") (pinfunction "1_1") (pintype "passive"))
      (node (ref "C35") (pin "1") (pinfunction "1_1") (pintype "passive"))
      (node (ref "C38") (pin "2") (pinfunction "2_2") (pintype "passive"))
      (node (ref "C39") (pin "2") (pinfunction "2_2") (pintype "passive"))
      (node (ref "C40") (pin "1") (pinfunction "1_1") (pintype "passive"))
      (node (ref "C47") (pin "2") (pinfunction "2_2") (pintype "passive"))
      (node (ref "C56") (pin "1") (pinfunction "1_1") (pintype "passive"))
      (node (ref "C61") (pin "1") (pinfunction "1_1") (pintype "passive"))
      (node (ref "C62") (pin "1") (pinfunction "1_1") (pintype "passive"))
      (node (ref "L2") (pin "2") (pinfunction "2_2") (pintype "passive"))
      (node (ref "R10") (pin "2") (pinfunction "2_2") (pintype "passive"))
      (node (ref "R11") (pin "2") (pinfunction "2_2") (pintype "passive"))
      (node (ref "R12") (pin "2") (pinfunction "2_2") (pintype "passive"))
      (node (ref "R22") (pin "2") (pinfunction "2_2") (pintype "passive"))
      (node (ref "R3") (pin "2") (pinfunction "2_2") (pintype "passive"))
      (node (ref "R52") (pin "2") (pinfunction "2_2") (pintype "passive"))
      (node (ref "R53") (pin "2") (pinfunction "2_2") (pintype "passive"))
      (node (ref "R54") (pin "2") (pinfunction "2_2") (pintype "passive"))
      (node (ref "R55") (pin "1") (pinfunction "1_1") (pintype "passive"))
      (node (ref "R56") (pin "2") (pinfunction "2_2") (pintype "passive"))
      (node (ref "R60") (pin "1") (pinfunction "1_1") (pintype "passive"))
      (node (ref "R7") (pin "2") (pinfunction "2_2") (pintype "passive"))
      (node (ref "R8") (pin "2") (pinfunction "2_2") (pintype "passive"))
      (node (ref "R9") (pin "2") (pinfunction "2_2") (pintype "passive"))
      (node (ref "U1") (pin "20") (pinfunction "VCC2_20") (pintype "passive"))
      (node (ref "U1") (pin "4") (pinfunction "HPVCC_4") (pintype "passive"))
      (node (ref "U1") (pin "5") (pinfunction "VCC1_5") (pintype "passive"))
      (node (ref "U1") (pin "50") (pinfunction "VCC3_50") (pintype "passive"))
      (node (ref "U1") (pin "67") (pinfunction "UVCC_67") (pintype "passive"))
      (node (ref "U1") (pin "73") (pinfunction "TVVCC_73") (pintype "passive"))
      (node (ref "U14") (pin "4") (pinfunction "VDD_4") (pintype "passive"))
      (node (ref "U15") (pin "3") (pinfunction "/WP(IO2)_3") (pintype "passive"))
      (node (ref "U15") (pin "7") (pinfunction "/HOLDor/RESET(IO3)_7") (pintype "passive"))
      (node (ref "U15") (pin "8") (pinfunction "VCC_8") (pintype "passive"))
      (node (ref "U25") (pin "3") (pinfunction "VIN_3") (pintype "passive"))
      (node (ref "U27") (pin "1") (pinfunction "1_1") (pintype "passive"))
      (node (ref "U27") (pin "3") (pinfunction "3_3") (pintype "passive"))
      (node (ref "U27") (pin "4") (pinfunction "4_4") (pintype "passive"))
      (node (ref "U27") (pin "6") (pinfunction "6_6") (pintype "passive"))
      (node (ref "U28") (pin "4") (pinfunction "4_4") (pintype "passive"))
      (node (ref "U31") (pin "10") (pinfunction "V+_10") (pintype "passive"))
      (node (ref "U33") (pin "10") (pinfunction "V+_10") (pintype "passive"))
      (node (ref "U35") (pin "10") (pinfunction "V+_10") (pintype "passive"))
    )
    (net (code "4") (name "/5V") (class "Default")
      (node (ref "C70") (pin "2") (pinfunction "2_2") (pintype "passive"))
      (node (ref "R57") (pin "1") (pinfunction "1_1") (pintype "passive"))
      (node (ref "SW1") (pin "1") (pinfunction "1_1") (pintype "passive"))
      (node (ref "U23") (pin "10") (pinfunction "VIN1_10") (pintype "passive"))
      (node (ref "U23") (pin "16") (pinfunction "VCC_16") (pintype "passive"))
      (node (ref "U23") (pin "18") (pinfunction "EN3_18") (pintype "passive"))
      (node (ref "U23") (pin "19") (pinfunction "VIN3_19") (pintype "passive"))
      (node (ref "U23") (pin "7") (pinfunction "VIN2_7") (pintype "passive"))
      (node (ref "U23") (pin "8") (pinfunction "EN2_8") (pintype "passive"))
      (node (ref "U23") (pin "9") (pinfunction "EN1_9") (pintype "passive"))
      (node (ref "U29") (pin "6") (pinfunction "6_6") (pintype "passive"))
      (node (ref "U32") (pin "11") (pinfunction "VDD5_11") (pintype "passive"))
      (node (ref "U37") (pin "2") (pinfunction "S_2") (pintype "passive"))
    )
    (net (code "5") (name "/ADC0") (class "Default")
      (node (ref "R50") (pin "1") (pinfunction "1_1") (pintype "passive"))
      (node (ref "R51") (pin "2") (pinfunction "2_2") (pintype "passive"))
      (node (ref "U1") (pin "79") (pinfunction "LRADCIN_79") (pintype "passive"))
    )
    (net (code "6") (name "/AVCC_3V0") (class "Default")
      (node (ref "C1") (pin "2") (pinfunction "2_2") (pintype "passive"))
      (node (ref "U1") (pin "80") (pinfunction "AVCC_80") (pintype "passive"))
      (node (ref "U25") (pin "2") (pinfunction "VOUT_2") (pintype "passive"))
    )
    (net (code "7") (name "/CAM_EN") (class "Default")
      (node (ref "Q2") (pin "1") (pinfunction "G_1") (pintype "passive"))
      (node (ref "R56") (pin "1") (pinfunction "1_1") (pintype "passive"))
      (node (ref "U1") (pin "37") (pinfunction "PE12/DA_MCLK_37") (pintype "passive"))
    )
    (net (code "8") (name "/CAM_N") (class "Default")
      (node (ref "U29") (pin "4") (pinfunction "4_4") (pintype "passive"))
      (node (ref "U31") (pin "6") (pinfunction "D-_6") (pintype "passive"))
    )
    (net (code "9") (name "/CAM_P") (class "Default")
      (node (ref "U29") (pin "3") (pinfunction "3_3") (pintype "passive"))
      (node (ref "U31") (pin "4") (pinfunction "D+_4") (pintype "passive"))
    )
    (net (code "10") (name "/EC_A") (class "Default")
      (node (ref "C69") (pin "2") (pinfunction "2_2") (pintype "passive"))
      (node (ref "R52") (pin "1") (pinfunction "1_1") (pintype "passive"))
      (node (ref "U34") (pin "A") (pinfunction "A_A") (pintype "passive"))
    )
    (net (code "11") (name "/EC_B") (class "Default")
      (node (ref "C68") (pin "2") (pinfunction "2_2") (pintype "passive"))
      (node (ref "R53") (pin "1") (pinfunction "1_1") (pintype "passive"))
      (node (ref "U34") (pin "B") (pinfunction "B_B") (pintype "passive"))
    )
    (net (code "12") (name "/EC_KEY") (class "Default")
      (node (ref "C67") (pin "2") (pinfunction "2_2") (pintype "passive"))
      (node (ref "R54") (pin "1") (pinfunction "1_1") (pintype "passive"))
      (node (ref "U34") (pin "S") (pinfunction "S_S") (pintype "passive"))
    )
    (net (code "13") (name "/KEY0") (class "Default")
      (node (ref "U1") (pin "38") (pinfunction "PE11/CLK_OUT_38") (pintype "passive"))
    )
    (net (code "14") (name "/KEY1") (class "Default")
      (node (ref "U1") (pin "44") (pinfunction "PE5/CSI_D2_44") (pintype "passive"))
    )
    (net (code "15") (name "/KEY2") (class "Default")
      (node (ref "U1") (pin "45") (pinfunction "PE4/CSI_D1_45") (pintype "passive"))
    )
    (net (code "16") (name "/KEY3") (class "Default")
      (node (ref "U1") (pin "47") (pinfunction "PE2/CSI_PCLK_47") (pintype "passive"))
    )
    (net (code "17") (name "/KEY4") (class "Default")
      (node (ref "U1") (pin "65") (pinfunction "PA1/TP_X2_65") (pintype "passive"))
    )
    (net (code "18") (name "/LCD_CS") (class "Default")
      (node (ref "U1") (pin "42") (pinfunction "PE7/CSI_D4_42") (pintype "passive"))
      (node (ref "U27") (pin "18") (pinfunction "18_18") (pintype "passive"))
    )
    (net (code "19") (name "/LCD_MOSI") (class "Default")
      (node (ref "U1") (pin "41") (pinfunction "PE8/CSI_D5_41") (pintype "passive"))
      (node (ref "U27") (pin "21") (pinfunction "21_21") (pintype "passive"))
    )
    (net (code "20") (name "/LCD_PWM") (class "Default")
      (node (ref "Q1") (pin "1") (pinfunction "G_1") (pintype "passive"))
      (node (ref "U1") (pin "43") (pinfunction "PE6/CSI_D3_43") (pintype "passive"))
    )
    (net (code "21") (name "/LCD_RES") (class "Default")
      (node (ref "U1") (pin "28") (pinfunction "PD20/HSYNC_28") (pintype "passive"))
      (node (ref "U27") (pin "20") (pinfunction "20_20") (pintype "passive"))
    )
    (net (code "22") (name "/LCD_RS{slash}CLK") (class "Default")
      (node (ref "U1") (pin "40") (pinfunction "PE9/CSI_D6_40") (pintype "passive"))
      (node (ref "U27") (pin "17") (pinfunction "17_17") (pintype "passive"))
    )
    (net (code "23") (name "/LCD_TE") (class "Default")
      (node (ref "U1") (pin "29") (pinfunction "PD21/VSYNC_29") (pintype "passive"))
      (node (ref "U27") (pin "19") (pinfunction "19_19") (pintype "passive"))
    )
    (net (code "24") (name "/LCD_WR{slash}DC") (class "Default")
      (node (ref "U1") (pin "39") (pinfunction "PE10/CSI_D7_39") (pintype "passive"))
      (node (ref "U27") (pin "16") (pinfunction "16_16") (pintype "passive"))
    )
    (net (code "25") (name "/LED0") (class "Default")
      (node (ref "LED3") (pin "1") (pinfunction "+_1") (pintype "passive"))
      (node (ref "U1") (pin "6") (pinfunction "PD0/LCD_D2_6") (pintype "passive"))
    )
    (net (code "26") (name "/RESET") (class "Default")
      (node (ref "C48") (pin "2") (pinfunction "2_2") (pintype "passive"))
      (node (ref "R12") (pin "1") (pinfunction "1_1") (pintype "passive"))
      (node (ref "U1") (pin "70") (pinfunction "RESET_70") (pintype "passive"))
    )
    (net (code "27") (name "/SD_CLK") (class "Default")
      (node (ref "U1") (pin "56") (pinfunction "PF2/SDC0_CLK_56") (pintype "passive"))
      (node (ref "U14") (pin "5") (pinfunction "CLK(SCLK)_5") (pintype "passive"))
    )
    (net (code "28") (name "/SD_CMD") (class "Default")
      (node (ref "R11") (pin "1") (pinfunction "1_1") (pintype "passive"))
      (node (ref "U1") (pin "55") (pinfunction "PF3/SDC0_CMD_55") (pintype "passive"))
      (node (ref "U14") (pin "3") (pinfunction "CMD(DI)_3") (pintype "passive"))
    )
    (net (code "29") (name "/SD_D0") (class "Default")
      (node (ref "R7") (pin "1") (pinfunction "1_1") (pintype "passive"))
      (node (ref "U1") (pin "57") (pinfunction "PF1/SDC0_D0_57") (pintype "passive"))
      (node (ref "U14") (pin "7") (pinfunction "DAT0(D0)_7") (pintype "passive"))
    )
    (net (code "30") (name "/SD_D1") (class "Default")
      (node (ref "R8") (pin "1") (pinfunction "1_1") (pintype "passive"))
      (node (ref "U1") (pin "58") (pinfunction "PF0/SDC0_D1_58") (pintype "passive"))
      (node (ref "U14") (pin "8") (pinfunction "DAT1(RSV)_8") (pintype "passive"))
    )
    (net (code "31") (name "/SD_D2") (class "Default")
      (node (ref "R10") (pin "1") (pinfunction "1_1") (pintype "passive"))
      (node (ref "U1") (pin "53") (pinfunction "PF5/SDC0_D2_53") (pintype "passive"))
      (node (ref "U14") (pin "1") (pinfunction "DAT2(RSV)_1") (pintype "passive"))
    )
    (net (code "32") (name "/SD_D3") (class "Default")
      (node (ref "R9") (pin "1") (pinfunction "1_1") (pintype "passive"))
      (node (ref "U1") (pin "54") (pinfunction "PF4/SDC0_D3_54") (pintype "passive"))
      (node (ref "U14") (pin "2") (pinfunction "CDDAT3(CS)_2") (pintype "passive"))
    )
    (net (code "33") (name "/SEL0HUB_N") (class "Default")
      (node (ref "U32") (pin "9") (pinfunction "DM_9") (pintype "passive"))
      (node (ref "U35") (pin "7") (pinfunction "HSD2-_7") (pintype "passive"))
    )
    (net (code "34") (name "/SEL0HUB_P") (class "Default")
      (node (ref "U32") (pin "10") (pinfunction "DP_10") (pintype "passive"))
      (node (ref "U35") (pin "3") (pinfunction "HSD2+_3") (pintype "passive"))
    )
    (net (code "35") (name "/SEL0SEL1_N") (class "Default")
      (node (ref "U33") (pin "7") (pinfunction "HSD2-_7") (pintype "passive"))
      (node (ref "U35") (pin "8") (pinfunction "HSD1-_8") (pintype "passive"))
    )
    (net (code "36") (name "/SEL0SEL1_P") (class "Default")
      (node (ref "U33") (pin "3") (pinfunction "HSD2+_3") (pintype "passive"))
      (node (ref "U35") (pin "2") (pinfunction "HSD1+_2") (pintype "passive"))
    )
    (net (code "37") (name "/SEL2HUB_N") (class "Default")
      (node (ref "U31") (pin "7") (pinfunction "HSD2-_7") (pintype "passive"))
      (node (ref "U32") (pin "7") (pinfunction "DM1_7") (pintype "passive"))
    )
    (net (code "38") (name "/SEL2HUB_P") (class "Default")
      (node (ref "U31") (pin "3") (pinfunction "HSD2+_3") (pintype "passive"))
      (node (ref "U32") (pin "8") (pinfunction "DP1_8") (pintype "passive"))
    )
    (net (code "39") (name "/SEL2SEL1_N") (class "Default")
      (node (ref "U31") (pin "8") (pinfunction "HSD1-_8") (pintype "passive"))
      (node (ref "U33") (pin "8") (pinfunction "HSD1-_8") (pintype "passive"))
    )
    (net (code "40") (name "/SEL2SEL1_P") (class "Default")
      (node (ref "U31") (pin "2") (pinfunction "HSD1+_2") (pintype "passive"))
      (node (ref "U33") (pin "2") (pinfunction "HSD1+_2") (pintype "passive"))
    )
    (net (code "41") (name "/SPI0_CLK") (class "Default")
      (node (ref "U1") (pin "59") (pinfunction "PC0/SPI0_CLK_59") (pintype "passive"))
      (node (ref "U15") (pin "6") (pinfunction "CLK_6") (pintype "passive"))
    )
    (net (code "42") (name "/SPI0_CS") (class "Default")
      (node (ref "R22") (pin "1") (pinfunction "1_1") (pintype "passive"))
      (node (ref "U1") (pin "60") (pinfunction "PC1/SPI0_CS_60") (pintype "passive"))
      (node (ref "U15") (pin "1") (pinfunction "/CS_1") (pintype "passive"))
    )
    (net (code "43") (name "/SPI0_MISO") (class "Default")
      (node (ref "U1") (pin "61") (pinfunction "PC2/SPI0_MISO_61") (pintype "passive"))
      (node (ref "U15") (pin "2") (pinfunction "DO(IO1)_2") (pintype "passive"))
    )
    (net (code "44") (name "/SPI0_MOSI") (class "Default")
      (node (ref "U1") (pin "62") (pinfunction "PC3/SPI0_MOSI_62") (pintype "passive"))
      (node (ref "U15") (pin "5") (pinfunction "DI(IO0)_5") (pintype "passive"))
    )
    (net (code "45") (name "/TYPEC_CC") (class "Default")
      (node (ref "R57") (pin "2") (pinfunction "2_2") (pintype "passive"))
      (node (ref "U2") (pin "10") (pinfunction "CC2_10") (pintype "passive"))
      (node (ref "U2") (pin "4") (pinfunction "CC1_4") (pintype "passive"))
      (node (ref "U37") (pin "1") (pinfunction "G_1") (pintype "passive"))
    )
    (net (code "46") (name "/UART1_RX") (class "Default")
      (node (ref "U1") (pin "9") (pinfunction "PD3/LCD_D5_9") (pintype "passive"))
      (node (ref "U28") (pin "3") (pinfunction "3_3") (pintype "passive"))
    )
    (net (code "47") (name "/UART1_TX") (class "Default")
      (node (ref "U1") (pin "10") (pinfunction "PD4/LCD_D6_10") (pintype "passive"))
      (node (ref "U28") (pin "2") (pinfunction "2_2") (pintype "passive"))
    )
    (net (code "48") (name "/USB_DEV_N") (class "Default")
      (node (ref "U33") (pin "6") (pinfunction "D-_6") (pintype "passive"))
      (node (ref "U38") (pin "5") (pinfunction "DN2_5") (pintype "passive"))
      (node (ref "U38") (pin "7") (pinfunction "DN1_7") (pintype "passive"))
    )
    (net (code "49") (name "/USB_DEV_P") (class "Default")
      (node (ref "U33") (pin "4") (pinfunction "D+_4") (pintype "passive"))
      (node (ref "U38") (pin "6") (pinfunction "DP1_6") (pintype "passive"))
      (node (ref "U38") (pin "8") (pinfunction "DP2_8") (pintype "passive"))
    )
    (net (code "50") (name "/USB_N") (class "Default")
      (node (ref "U2") (pin "5") (pinfunction "DN2_5") (pintype "passive"))
      (node (ref "U2") (pin "7") (pinfunction "DN1_7") (pintype "passive"))
      (node (ref "U32") (pin "5") (pinfunction "DM2_5") (pintype "passive"))
    )
    (net (code "51") (name "/USB_P") (class "Default")
      (node (ref "U2") (pin "6") (pinfunction "DP1_6") (pintype "passive"))
      (node (ref "U2") (pin "8") (pinfunction "DP2_8") (pintype "passive"))
      (node (ref "U32") (pin "6") (pinfunction "DP2_6") (pintype "passive"))
    )
    (net (code "52") (name "/USB_SEL0") (class "Default")
      (node (ref "R55") (pin "2") (pinfunction "2_2") (pintype "passive"))
      (node (ref "SW18") (pin "2") (pinfunction "2_2") (pintype "passive"))
      (node (ref "U1") (pin "49") (pinfunction "PE0/CSI_HSYNC_49") (pintype "passive"))
      (node (ref "U35") (pin "1") (pinfunction "S_1") (pintype "passive"))
    )
    (net (code "53") (name "/USB_SEL12") (class "Default")
      (node (ref "R60") (pin "2") (pinfunction "2_2") (pintype "passive"))
      (node (ref "SW12") (pin "2") (pinfunction "2_2") (pintype "passive"))
      (node (ref "U1") (pin "48") (pinfunction "PE1/CSI_VSYNC_48") (pintype "passive"))
      (node (ref "U31") (pin "1") (pinfunction "S_1") (pintype "passive"))
      (node (ref "U33") (pin "1") (pinfunction "S_1") (pintype "passive"))
    )
    (net (code "54") (name "/U_N") (class "Default")
      (node (ref "U1") (pin "68") (pinfunction "DM_68") (pintype "passive"))
      (node (ref "U35") (pin "6") (pinfunction "D-_6") (pintype "passive"))
    )
    (net (code "55") (name "/U_P") (class "Default")
      (node (ref "U1") (pin "69") (pinfunction "DP_69") (pintype "passive"))
      (node (ref "U35") (pin "4") (pinfunction "D+_4") (pintype "passive"))
    )
    (net (code "56") (name "/VBUS") (class "Default")
      (node (ref "C44") (pin "2") (pinfunction "2_2") (pintype "passive"))
      (node (ref "R32") (pin "2") (pinfunction "2_2") (pintype "passive"))
      (node (ref "U26") (pin "7") (pinfunction "VIN_7") (pintype "passive"))
      (node (ref "U38") (pin "11") (pinfunction "VBUS_11") (pintype "passive"))
      (node (ref "U38") (pin "2") (pinfunction "VBUS_2") (pintype "passive"))
    )
    (net (code "57") (name "/VHOST") (class "Default")
      (node (ref "C64") (pin "1") (pinfunction "1_1") (pintype "passive"))
      (node (ref "C65") (pin "1") (pinfunction "1_1") (pintype "passive"))
      (node (ref "C66") (pin "1") (pinfunction "1_1") (pintype "passive"))
      (node (ref "D1") (pin "1") (pinfunction "K_1") (pintype "passive"))
      (node (ref "U2") (pin "11") (pinfunction "VBUS_11") (pintype "passive"))
      (node (ref "U2") (pin "2") (pinfunction "VBUS_2") (pintype "passive"))
    )
    (net (code "58") (name "GND") (class "Default")
      (node (ref "C1") (pin "1") (pinfunction "1_1") (pintype "passive"))
      (node (ref "C10") (pin "1") (pinfunction "1_1") (pintype "passive"))
      (node (ref "C12") (pin "1") (pinfunction "1_1") (pintype "passive"))
      (node (ref "C13") (pin "2") (pinfunction "2_2") (pintype "passive"))
      (node (ref "C14") (pin "2") (pinfunction "2_2") (pintype "passive"))
      (node (ref "C15") (pin "2") (pinfunction "2_2") (pintype "passive"))
      (node (ref "C2") (pin "1") (pinfunction "1_1") (pintype "passive"))
      (node (ref "C20") (pin "2") (pinfunction "2_2") (pintype "passive"))
      (node (ref "C21") (pin "1") (pinfunction "1_1") (pintype "passive"))
      (node (ref "C22") (pin "2") (pinfunction "2_2") (pintype "passive"))
      (node (ref "C32") (pin "2") (pinfunction "2_2") (pintype "passive"))
      (node (ref "C33") (pin "2") (pinfunction "2_2") (pintype "passive"))
      (node (ref "C34") (pin "2") (pinfunction "2_2") (pintype "passive"))
      (node (ref "C35") (pin "2") (pinfunction "2_2") (pintype "passive"))
      (node (ref "C36") (pin "2") (pinfunction "2_2") (pintype "passive"))
      (node (ref "C37") (pin "2") (pinfunction "2_2") (pintype "passive"))
      (node (ref "C38") (pin "1") (pinfunction "1_1") (pintype "passive"))
      (node (ref "C39") (pin "1") (pinfunction "1_1") (pintype "passive"))
      (node (ref "C40") (pin "2") (pinfunction "2_2") (pintype "passive"))
      (node (ref "C42") (pin "1") (pinfunction "1_1") (pintype "passive"))
      (node (ref "C43") (pin "1") (pinfunction "1_1") (pintype "passive"))
      (node (ref "C44") (pin "1") (pinfunction "1_1") (pintype "passive"))
      (node (ref "C45") (pin "1") (pinfunction "1_1") (pintype "passive"))
      (node (ref "C46") (pin "1") (pinfunction "1_1") (pintype "passive"))
      (node (ref "C47") (pin "1") (pinfunction "1_1") (pintype "passive"))
      (node (ref "C48") (pin "1") (pinfunction "1_1") (pintype "passive"))
      (node (ref "C56") (pin "2") (pinfunction "2_2") (pintype "passive"))
      (node (ref "C57") (pin "1") (pinfunction "1_1") (pintype "passive"))
      (node (ref "C58") (pin "1") (pinfunction "1_1") (pintype "passive"))
      (node (ref "C59") (pin "1") (pinfunction "1_1") (pintype "passive"))
      (node (ref "C60") (pin "1") (pinfunction "1_1") (pintype "passive"))
      (node (ref "C61") (pin "2") (pinfunction "2_2") (pintype "passive"))
      (node (ref "C62") (pin "2") (pinfunction "2_2") (pintype "passive"))
      (node (ref "C64") (pin "2") (pinfunction "2_2") (pintype "passive"))
      (node (ref "C65") (pin "2") (pinfunction "2_2") (pintype "passive"))
      (node (ref "C66") (pin "2") (pinfunction "2_2") (pintype "passive"))
      (node (ref "C67") (pin "1") (pinfunction "1_1") (pintype "passive"))
      (node (ref "C68") (pin "1") (pinfunction "1_1") (pintype "passive"))
      (node (ref "C69") (pin "1") (pinfunction "1_1") (pintype "passive"))
      (node (ref "C70") (pin "1") (pinfunction "1_1") (pintype "passive"))
      (node (ref "C9") (pin "2") (pinfunction "2_2") (pintype "passive"))
      (node (ref "LED1") (pin "1") (pinfunction "K_1") (pintype "passive"))
      (node (ref "Q1") (pin "2") (pinfunction "S_2") (pintype "passive"))
      (node (ref "Q2") (pin "2") (pinfunction "S_2") (pintype "passive"))
      (node (ref "R2") (pin "1") (pinfunction "1_1") (pintype "passive"))
      (node (ref "R24") (pin "2") (pinfunction "2_2") (pintype "passive"))
      (node (ref "R25") (pin "1") (pinfunction "1_1") (pintype "passive"))
      (node (ref "R31") (pin "2") (pinfunction "2_2") (pintype "passive"))
      (node (ref "R32") (pin "1") (pinfunction "1_1") (pintype "passive"))
      (node (ref "R34") (pin "1") (pinfunction "1_1") (pintype "passive"))
      (node (ref "R4") (pin "1") (pinfunction "1_1") (pintype "passive"))
      (node (ref "R44") (pin "2") (pinfunction "2_2") (pintype "passive"))
      (node (ref "R51") (pin "1") (pinfunction "1_1") (pintype "passive"))
      (node (ref "R6") (pin "1") (pinfunction "1_1") (pintype "passive"))
      (node (ref "R61") (pin "1") (pinfunction "1_1") (pintype "passive"))
      (node (ref "R62") (pin "1") (pinfunction "1_1") (pintype "passive"))
      (node (ref "SW1") (pin "4") (pinfunction "4_4") (pintype "passive"))
      (node (ref "SW12") (pin "3") (pinfunction "3_3") (pintype "passive"))
      (node (ref "SW12") (pin "4") (pinfunction "4_4") (pintype "passive"))
      (node (ref "SW18") (pin "1") (pinfunction "1_1") (pintype "passive"))
      (node (ref "SW18") (pin "4") (pinfunction "4_4") (pintype "passive"))
      (node (ref "U1") (pin "74") (pinfunction "TVGND_74") (pintype "passive"))
      (node (ref "U1") (pin "82") (pinfunction "AGND_82") (pintype "passive"))
      (node (ref "U1") (pin "89") (pinfunction "GND_89") (pintype "passive"))
      (node (ref "U13") (pin "2") (pinfunction "GND_2") (pintype "passive"))
      (node (ref "U13") (pin "4") (pinfunction "GND_4") (pintype "passive"))
      (node (ref "U14") (pin "10") (pinfunction "GND_10") (pintype "passive"))
      (node (ref "U14") (pin "11") (pinfunction "GND_11") (pintype "passive"))
      (node (ref "U14") (pin "12") (pinfunction "GND_12") (pintype "passive"))
      (node (ref "U14") (pin "13") (pinfunction "GND_13") (pintype "passive"))
      (node (ref "U14") (pin "6") (pinfunction "VSS_6") (pintype "passive"))
      (node (ref "U14") (pin "9") (pinfunction "CD_9") (pintype "passive"))
      (node (ref "U15") (pin "4") (pinfunction "GND_4") (pintype "passive"))
      (node (ref "U15") (pin "9") (pinfunction "EP_9") (pintype "passive"))
      (node (ref "U2") (pin "1") (pinfunction "GND_1") (pintype "passive"))
      (node (ref "U2") (pin "12") (pinfunction "GND_12") (pintype "passive"))
      (node (ref "U2") (pin "13") (pinfunction "SHELL_13") (pintype "passive"))
      (node (ref "U2") (pin "14") (pinfunction "SHELL_14") (pintype "passive"))
      (node (ref "U23") (pin "1") (pinfunction "GND3_1") (pintype "passive"))
      (node (ref "U23") (pin "12") (pinfunction "GND1_12") (pintype "passive"))
      (node (ref "U23") (pin "13") (pinfunction "GND1_13") (pintype "passive"))
      (node (ref "U23") (pin "15") (pinfunction "AGND_15") (pintype "passive"))
      (node (ref "U23") (pin "17") (pinfunction "AGND_17") (pintype "passive"))
      (node (ref "U23") (pin "21") (pinfunction "EP_21") (pintype "passive"))
      (node (ref "U23") (pin "4") (pinfunction "GND2_4") (pintype "passive"))
      (node (ref "U23") (pin "5") (pinfunction "GND2_5") (pintype "passive"))
      (node (ref "U25") (pin "1") (pinfunction "VSS_1") (pintype "passive"))
      (node (ref "U26") (pin "1") (pinfunction "NTC_1") (pintype "passive"))
      (node (ref "U26") (pin "9") (pinfunction "EP_9") (pintype "passive"))
      (node (ref "U27") (pin "10") (pinfunction "10_10") (pintype "passive"))
      (node (ref "U27") (pin "11") (pinfunction "11_11") (pintype "passive"))
      (node (ref "U27") (pin "12") (pinfunction "12_12") (pintype "passive"))
      (node (ref "U27") (pin "13") (pinfunction "13_13") (pintype "passive"))
      (node (ref "U27") (pin "14") (pinfunction "14_14") (pintype "passive"))
      (node (ref "U27") (pin "15") (pinfunction "15_15") (pintype "passive"))
      (node (ref "U27") (pin "22") (pinfunction "22_22") (pintype "passive"))
      (node (ref "U27") (pin "23") (pinfunction "23_23") (pintype "passive"))
      (node (ref "U27") (pin "24") (pinfunction "24_24") (pintype "passive"))
      (node (ref "U27") (pin "5") (pinfunction "5_5") (pintype "passive"))
      (node (ref "U27") (pin "7") (pinfunction "7_7") (pintype "passive"))
      (node (ref "U27") (pin "8") (pinfunction "8_8") (pintype "passive"))
      (node (ref "U27") (pin "9") (pinfunction "9_9") (pintype "passive"))
      (node (ref "U28") (pin "1") (pinfunction "1_1") (pintype "passive"))
      (node (ref "U30") (pin "1") (pinfunction "1_1") (pintype "passive"))
      (node (ref "U31") (pin "5") (pinfunction "GND_5") (pintype "passive"))
      (node (ref "U31") (pin "9") (pinfunction "OE_9") (pintype "passive"))
      (node (ref "U32") (pin "12") (pinfunction "GND_12") (pintype "passive"))
      (node (ref "U33") (pin "5") (pinfunction "GND_5") (pintype "passive"))
      (node (ref "U33") (pin "9") (pinfunction "OE_9") (pintype "passive"))
      (node (ref "U34") (pin "1") (pinfunction "EH_1") (pintype "passive"))
      (node (ref "U34") (pin "2") (pinfunction "EH_2") (pintype "passive"))
      (node (ref "U34") (pin "3") (pinfunction "EH_3") (pintype "passive"))
      (node (ref "U34") (pin "4") (pinfunction "EH_4") (pintype "passive"))
      (node (ref "U34") (pin "5") (pinfunction "EH_5") (pintype "passive"))
      (node (ref "U34") (pin "6") (pinfunction "EH_6") (pintype "passive"))
      (node (ref "U34") (pin "C") (pinfunction "C_C") (pintype "passive"))
      (node (ref "U35") (pin "5") (pinfunction "GND_5") (pintype "passive"))
      (node (ref "U35") (pin "9") (pinfunction "OE_9") (pintype "passive"))
      (node (ref "U38") (pin "1") (pinfunction "GND_1") (pintype "passive"))
      (node (ref "U38") (pin "12") (pinfunction "GND_12") (pintype "passive"))
      (node (ref "U38") (pin "13") (pinfunction "SHELL_13") (pintype "passive"))
      (node (ref "U38") (pin "14") (pinfunction "SHELL_14") (pintype "passive"))
      (node (ref "X1") (pin "2") (pinfunction "GND_2") (pintype "passive"))
      (node (ref "X1") (pin "4") (pinfunction "GND_4") (pintype "passive"))
    )
    (net (code "59") (name "Net-(C45-Pad2)") (class "Default")
      (node (ref "C45") (pin "2") (pinfunction "2_2") (pintype "passive"))
      (node (ref "C46") (pin "2") (pinfunction "2_2") (pintype "passive"))
      (node (ref "SW1") (pin "2") (pinfunction "2_2") (pintype "passive"))
      (node (ref "SW1") (pin "3") (pinfunction "3_3") (pintype "passive"))
      (node (ref "U26") (pin "3") (pinfunction "VH_3") (pintype "passive"))
      (node (ref "U26") (pin "4") (pinfunction "VH_4") (pintype "passive"))
    )
    (net (code "60") (name "Net-(D1-A)") (class "Default")
      (node (ref "D1") (pin "2") (pinfunction "A_2") (pintype "passive"))
      (node (ref "U37") (pin "3") (pinfunction "D_3") (pintype "passive"))
    )
    (net (code "61") (name "Net-(LED1-A)") (class "Default")
      (node (ref "LED1") (pin "2") (pinfunction "A_2") (pintype "passive"))
      (node (ref "R33") (pin "2") (pinfunction "2_2") (pintype "passive"))
    )
    (net (code "62") (name "Net-(LED3--)") (class "Default")
      (node (ref "LED3") (pin "2") (pinfunction "-_2") (pintype "passive"))
      (node (ref "R44") (pin "1") (pinfunction "1_1") (pintype "passive"))
    )
    (net (code "63") (name "Net-(Q1-D)") (class "Default")
      (node (ref "Q1") (pin "3") (pinfunction "D_3") (pintype "passive"))
      (node (ref "R37") (pin "1") (pinfunction "1_1") (pintype "passive"))
    )
    (net (code "64") (name "Net-(Q2-D)") (class "Default")
      (node (ref "Q2") (pin "3") (pinfunction "D_3") (pintype "passive"))
      (node (ref "U29") (pin "1") (pinfunction "1_1") (pintype "passive"))
      (node (ref "U29") (pin "2") (pinfunction "2_2") (pintype "passive"))
    )
    (net (code "65") (name "Net-(R37-Pad2)") (class "Default")
      (node (ref "R37") (pin "2") (pinfunction "2_2") (pintype "passive"))
      (node (ref "U27") (pin "2") (pinfunction "2_2") (pintype "passive"))
    )
    (net (code "66") (name "Net-(U1-AVRA1)") (class "Default")
      (node (ref "C15") (pin "1") (pinfunction "1_1") (pintype "passive"))
      (node (ref "U1") (pin "81") (pinfunction "AVRA1_81") (pintype "passive"))
    )
    (net (code "67") (name "Net-(U1-AVRA2)") (class "Default")
      (node (ref "C13") (pin "1") (pinfunction "1_1") (pintype "passive"))
      (node (ref "C14") (pin "1") (pinfunction "1_1") (pintype "passive"))
      (node (ref "R25") (pin "2") (pinfunction "2_2") (pintype "passive"))
      (node (ref "U1") (pin "83") (pinfunction "AVRA2_83") (pintype "passive"))
    )
    (net (code "68") (name "Net-(U1-DRAM_VREF)") (class "Default")
      (node (ref "C11") (pin "1") (pinfunction "1_1") (pintype "passive"))
      (node (ref "C12") (pin "2") (pinfunction "2_2") (pintype "passive"))
      (node (ref "R23") (pin "2") (pinfunction "2_2") (pintype "passive"))
      (node (ref "R24") (pin "1") (pinfunction "1_1") (pintype "passive"))
      (node (ref "U1") (pin "33") (pinfunction "DRAM_VREF_33") (pintype "passive"))
    )
    (net (code "69") (name "Net-(U1-HOSCI)") (class "Default")
      (node (ref "C10") (pin "2") (pinfunction "2_2") (pintype "passive"))
      (node (ref "U1") (pin "51") (pinfunction "HOSCI_51") (pintype "passive"))
      (node (ref "U13") (pin "1") (pinfunction "OSC1_1") (pintype "passive"))
    )
    (net (code "70") (name "Net-(U1-HOSCO)") (class "Default")
      (node (ref "C9") (pin "1") (pinfunction "1_1") (pintype "passive"))
      (node (ref "U1") (pin "52") (pinfunction "HOSCO_52") (pintype "passive"))
      (node (ref "U13") (pin "3") (pinfunction "OSC2_3") (pintype "passive"))
    )
    (net (code "71") (name "Net-(U1-HPCOM)") (class "Default")
      (node (ref "R27") (pin "1") (pinfunction "1_1") (pintype "passive"))
      (node (ref "U1") (pin "3") (pinfunction "HPCOM_3") (pintype "passive"))
    )
    (net (code "72") (name "Net-(U1-HPCOM_FB)") (class "Default")
      (node (ref "C22") (pin "1") (pinfunction "1_1") (pintype "passive"))
      (node (ref "R27") (pin "2") (pinfunction "2_2") (pintype "passive"))
      (node (ref "U1") (pin "2") (pinfunction "HPCOM_FB_2") (pintype "passive"))
    )
    (net (code "73") (name "Net-(U23-FB1)") (class "Default")
      (node (ref "R5") (pin "1") (pinfunction "1_1") (pintype "passive"))
      (node (ref "R6") (pin "2") (pinfunction "2_2") (pintype "passive"))
      (node (ref "U23") (pin "14") (pinfunction "FB1_14") (pintype "passive"))
    )
    (net (code "74") (name "Net-(U23-FB2)") (class "Default")
      (node (ref "R3") (pin "1") (pinfunction "1_1") (pintype "passive"))
      (node (ref "R4") (pin "2") (pinfunction "2_2") (pintype "passive"))
      (node (ref "U23") (pin "3") (pinfunction "FB2_3") (pintype "passive"))
    )
    (net (code "75") (name "Net-(U23-FB3)") (class "Default")
      (node (ref "R1") (pin "1") (pinfunction "1_1") (pintype "passive"))
      (node (ref "R2") (pin "2") (pinfunction "2_2") (pintype "passive"))
      (node (ref "U23") (pin "2") (pinfunction "FB3_2") (pintype "passive"))
    )
    (net (code "76") (name "Net-(U23-LX1)") (class "Default")
      (node (ref "L3") (pin "1") (pinfunction "1_1") (pintype "passive"))
      (node (ref "U23") (pin "11") (pinfunction "LX1_11") (pintype "passive"))
    )
    (net (code "77") (name "Net-(U23-LX2)") (class "Default")
      (node (ref "L2") (pin "1") (pinfunction "1_1") (pintype "passive"))
      (node (ref "U23") (pin "6") (pinfunction "LX2_6") (pintype "passive"))
    )
    (net (code "78") (name "Net-(U23-LX3)") (class "Default")
      (node (ref "L1") (pin "1") (pinfunction "1_1") (pintype "passive"))
      (node (ref "U23") (pin "20") (pinfunction "LX3_20") (pintype "passive"))
    )
    (net (code "79") (name "Net-(U26-ISET)") (class "Default")
      (node (ref "R31") (pin "1") (pinfunction "1_1") (pintype "passive"))
      (node (ref "U26") (pin "8") (pinfunction "ISET_8") (pintype "passive"))
    )
    (net (code "80") (name "Net-(U26-LX)") (class "Default")
      (node (ref "L4") (pin "1") (pinfunction "1_1") (pintype "passive"))
      (node (ref "U26") (pin "5") (pinfunction "LX_5") (pintype "passive"))
    )
    (net (code "81") (name "Net-(U26-VL)") (class "Default")
      (node (ref "C42") (pin "2") (pinfunction "2_2") (pintype "passive"))
      (node (ref "C43") (pin "2") (pinfunction "2_2") (pintype "passive"))
      (node (ref "L4") (pin "2") (pinfunction "2_2") (pintype "passive"))
      (node (ref "R50") (pin "2") (pinfunction "2_2") (pintype "passive"))
      (node (ref "U26") (pin "6") (pinfunction "VL_6") (pintype "passive"))
      (node (ref "U30") (pin "2") (pinfunction "2_2") (pintype "passive"))
    )
    (net (code "82") (name "Net-(U26-VSET(LED))") (class "Default")
      (node (ref "R33") (pin "1") (pinfunction "1_1") (pintype "passive"))
      (node (ref "R34") (pin "2") (pinfunction "2_2") (pintype "passive"))
      (node (ref "U26") (pin "2") (pinfunction "VSET(LED)_2") (pintype "passive"))
    )
    (net (code "83") (name "Net-(U32-VDD18)") (class "Default")
      (node (ref "C59") (pin "2") (pinfunction "2_2") (pintype "passive"))
      (node (ref "U32") (pin "14") (pinfunction "VDD18_14") (pintype "passive"))
    )
    (net (code "84") (name "Net-(U32-VDD33)") (class "Default")
      (node (ref "C60") (pin "2") (pinfunction "2_2") (pintype "passive"))
      (node (ref "U32") (pin "13") (pinfunction "VDD33_13") (pintype "passive"))
    )
    (net (code "85") (name "Net-(U32-XIN)") (class "Default")
      (node (ref "C57") (pin "2") (pinfunction "2_2") (pintype "passive"))
      (node (ref "U32") (pin "16") (pinfunction "XIN_16") (pintype "passive"))
      (node (ref "X1") (pin "3") (pinfunction "OSC2_3") (pintype "passive"))
    )
    (net (code "86") (name "Net-(U32-XOUT)") (class "Default")
      (node (ref "C58") (pin "2") (pinfunction "2_2") (pintype "passive"))
      (node (ref "U32") (pin "15") (pinfunction "XOUT_15") (pintype "passive"))
      (node (ref "X1") (pin "1") (pinfunction "OSC1_1") (pintype "passive"))
    )
    (net (code "87") (name "Net-(U38-CC1)") (class "Default")
      (node (ref "R61") (pin "2") (pinfunction "2_2") (pintype "passive"))
      (node (ref "U38") (pin "4") (pinfunction "CC1_4") (pintype "passive"))
    )
    (net (code "88") (name "Net-(U38-CC2)") (class "Default")
      (node (ref "R62") (pin "2") (pinfunction "2_2") (pintype "passive"))
      (node (ref "U38") (pin "10") (pinfunction "CC2_10") (pintype "passive"))
    )
    (net (code "89") (name "unconnected-(SW12-Pad1)") (class "Default")
      (node (ref "SW12") (pin "1") (pinfunction "1_1") (pintype "passive"))
    )
    (net (code "90") (name "unconnected-(SW18-Pad3)") (class "Default")
      (node (ref "SW18") (pin "3") (pinfunction "3_3") (pintype "passive"))
    )
    (net (code "91") (name "unconnected-(U1-FMINL-Pad84)") (class "Default")
      (node (ref "U1") (pin "84") (pinfunction "FMINL_84") (pintype "passive"))
    )
    (net (code "92") (name "unconnected-(U1-FMINR-Pad85)") (class "Default")
      (node (ref "U1") (pin "85") (pinfunction "FMINR_85") (pintype "passive"))
    )
    (net (code "93") (name "unconnected-(U1-HPL-Pad1)") (class "Default")
      (node (ref "U1") (pin "1") (pinfunction "HPL_1") (pintype "passive"))
    )
    (net (code "94") (name "unconnected-(U1-HPR-Pad88)") (class "Default")
      (node (ref "U1") (pin "88") (pinfunction "HPR_88") (pintype "passive"))
    )
    (net (code "95") (name "unconnected-(U1-LINL-Pad86)") (class "Default")
      (node (ref "U1") (pin "86") (pinfunction "LINL_86") (pintype "passive"))
    )
    (net (code "96") (name "unconnected-(U1-MICIN-Pad87)") (class "Default")
      (node (ref "U1") (pin "87") (pinfunction "MICIN_87") (pintype "passive"))
    )
    (net (code "97") (name "unconnected-(U1-PA0{slash}TP_X1-Pad66)") (class "Default")
      (node (ref "U1") (pin "66") (pinfunction "PA0/TP_X1_66") (pintype "passive"))
    )
    (net (code "98") (name "unconnected-(U1-PA2{slash}TP_Y1-Pad64)") (class "Default")
      (node (ref "U1") (pin "64") (pinfunction "PA2/TP_Y1_64") (pintype "passive"))
    )
    (net (code "99") (name "unconnected-(U1-PA3{slash}TP_Y2-Pad63)") (class "Default")
      (node (ref "U1") (pin "63") (pinfunction "PA3/TP_Y2_63") (pintype "passive"))
    )
    (net (code "100") (name "unconnected-(U1-PD1{slash}LCD_D3-Pad7)") (class "Default")
      (node (ref "U1") (pin "7") (pinfunction "PD1/LCD_D3_7") (pintype "passive"))
    )
    (net (code "101") (name "unconnected-(U1-PD2{slash}LCD_D4-Pad8)") (class "Default")
      (node (ref "U1") (pin "8") (pinfunction "PD2/LCD_D4_8") (pintype "passive"))
    )
    (net (code "102") (name "unconnected-(U1-PD5{slash}LCD_D7-Pad11)") (class "Default")
      (node (ref "U1") (pin "11") (pinfunction "PD5/LCD_D7_11") (pintype "passive"))
    )
    (net (code "103") (name "unconnected-(U1-PD6{slash}LCD_D10-Pad12)") (class "Default")
      (node (ref "U1") (pin "12") (pinfunction "PD6/LCD_D10_12") (pintype "passive"))
    )
    (net (code "104") (name "unconnected-(U1-PD7{slash}LCD_D11-Pad13)") (class "Default")
      (node (ref "U1") (pin "13") (pinfunction "PD7/LCD_D11_13") (pintype "passive"))
    )
    (net (code "105") (name "unconnected-(U1-PD8{slash}LCD_D12-Pad14)") (class "Default")
      (node (ref "U1") (pin "14") (pinfunction "PD8/LCD_D12_14") (pintype "passive"))
    )
    (net (code "106") (name "unconnected-(U1-PD9{slash}LCD_D13-Pad15)") (class "Default")
      (node (ref "U1") (pin "15") (pinfunction "PD9/LCD_D13_15") (pintype "passive"))
    )
    (net (code "107") (name "unconnected-(U1-PD10{slash}LCD_D14-Pad16)") (class "Default")
      (node (ref "U1") (pin "16") (pinfunction "PD10/LCD_D14_16") (pintype "passive"))
    )
    (net (code "108") (name "unconnected-(U1-PD11{slash}LCD_D15-Pad17)") (class "Default")
      (node (ref "U1") (pin "17") (pinfunction "PD11/LCD_D15_17") (pintype "passive"))
    )
    (net (code "109") (name "unconnected-(U1-PD12{slash}LCD_D18-Pad18)") (class "Default")
      (node (ref "U1") (pin "18") (pinfunction "PD12/LCD_D18_18") (pintype "passive"))
    )
    (net (code "110") (name "unconnected-(U1-PD13{slash}LCD_D19-Pad19)") (class "Default")
      (node (ref "U1") (pin "19") (pinfunction "PD13/LCD_D19_19") (pintype "passive"))
    )
    (net (code "111") (name "unconnected-(U1-PD14{slash}LCD_D20-Pad21)") (class "Default")
      (node (ref "U1") (pin "21") (pinfunction "PD14/LCD_D20_21") (pintype "passive"))
    )
    (net (code "112") (name "unconnected-(U1-PD15{slash}LCD_D21-Pad23)") (class "Default")
      (node (ref "U1") (pin "23") (pinfunction "PD15/LCD_D21_23") (pintype "passive"))
    )
    (net (code "113") (name "unconnected-(U1-PD16{slash}LCD_D22-Pad24)") (class "Default")
      (node (ref "U1") (pin "24") (pinfunction "PD16/LCD_D22_24") (pintype "passive"))
    )
    (net (code "114") (name "unconnected-(U1-PD17{slash}LCD_D23-Pad25)") (class "Default")
      (node (ref "U1") (pin "25") (pinfunction "PD17/LCD_D23_25") (pintype "passive"))
    )
    (net (code "115") (name "unconnected-(U1-PD18{slash}LCD_CLK-Pad26)") (class "Default")
      (node (ref "U1") (pin "26") (pinfunction "PD18/LCD_CLK_26") (pintype "passive"))
    )
    (net (code "116") (name "unconnected-(U1-PD19{slash}LCD_DE-Pad27)") (class "Default")
      (node (ref "U1") (pin "27") (pinfunction "PD19/LCD_DE_27") (pintype "passive"))
    )
    (net (code "117") (name "unconnected-(U1-PE3{slash}CSI_D0-Pad46)") (class "Default")
      (node (ref "U1") (pin "46") (pinfunction "PE3/CSI_D0_46") (pintype "passive"))
    )
    (net (code "118") (name "unconnected-(U1-TVIN0-Pad78)") (class "Default")
      (node (ref "U1") (pin "78") (pinfunction "TVIN0_78") (pintype "passive"))
    )
    (net (code "119") (name "unconnected-(U1-TVIN1-Pad77)") (class "Default")
      (node (ref "U1") (pin "77") (pinfunction "TVIN1_77") (pintype "passive"))
    )
    (net (code "120") (name "unconnected-(U1-TVOUT-Pad72)") (class "Default")
      (node (ref "U1") (pin "72") (pinfunction "TVOUT_72") (pintype "passive"))
    )
    (net (code "121") (name "unconnected-(U1-TV_VRN-Pad75)") (class "Default")
      (node (ref "U1") (pin "75") (pinfunction "TV_VRN_75") (pintype "passive"))
    )
    (net (code "122") (name "unconnected-(U1-TV_VRP-Pad76)") (class "Default")
      (node (ref "U1") (pin "76") (pinfunction "TV_VRP_76") (pintype "passive"))
    )
    (net (code "123") (name "unconnected-(U2-SBU1-Pad9)") (class "Default")
      (node (ref "U2") (pin "9") (pinfunction "SBU1_9") (pintype "passive"))
    )
    (net (code "124") (name "unconnected-(U2-SBU2-Pad3)") (class "Default")
      (node (ref "U2") (pin "3") (pinfunction "SBU2_3") (pintype "passive"))
    )
    (net (code "125") (name "unconnected-(U29-Pad5)") (class "Default")
      (node (ref "U29") (pin "5") (pinfunction "5_5") (pintype "passive"))
    )
    (net (code "126") (name "unconnected-(U32-DM3-Pad3)") (class "Default")
      (node (ref "U32") (pin "3") (pinfunction "DM3_3") (pintype "passive"))
    )
    (net (code "127") (name "unconnected-(U32-DM4-Pad1)") (class "Default")
      (node (ref "U32") (pin "1") (pinfunction "DM4_1") (pintype "passive"))
    )
    (net (code "128") (name "unconnected-(U32-DP3-Pad4)") (class "Default")
      (node (ref "U32") (pin "4") (pinfunction "DP3_4") (pintype "passive"))
    )
    (net (code "129") (name "unconnected-(U32-DP4-Pad2)") (class "Default")
      (node (ref "U32") (pin "2") (pinfunction "DP4_2") (pintype "passive"))
    )
    (net (code "130") (name "unconnected-(U38-SBU1-Pad9)") (class "Default")
      (node (ref "U38") (pin "9") (pinfunction "SBU1_9") (pintype "passive"))
    )
    (net (code "131") (name "unconnected-(U38-SBU2-Pad3)") (class "Default")
      (node (ref "U38") (pin "3") (pinfunction "SBU2_3") (pintype "passive"))
    )
  )
)
